# CntrlBoardV3B.net
KiCad netlist of a schematic drawn in EAGLE
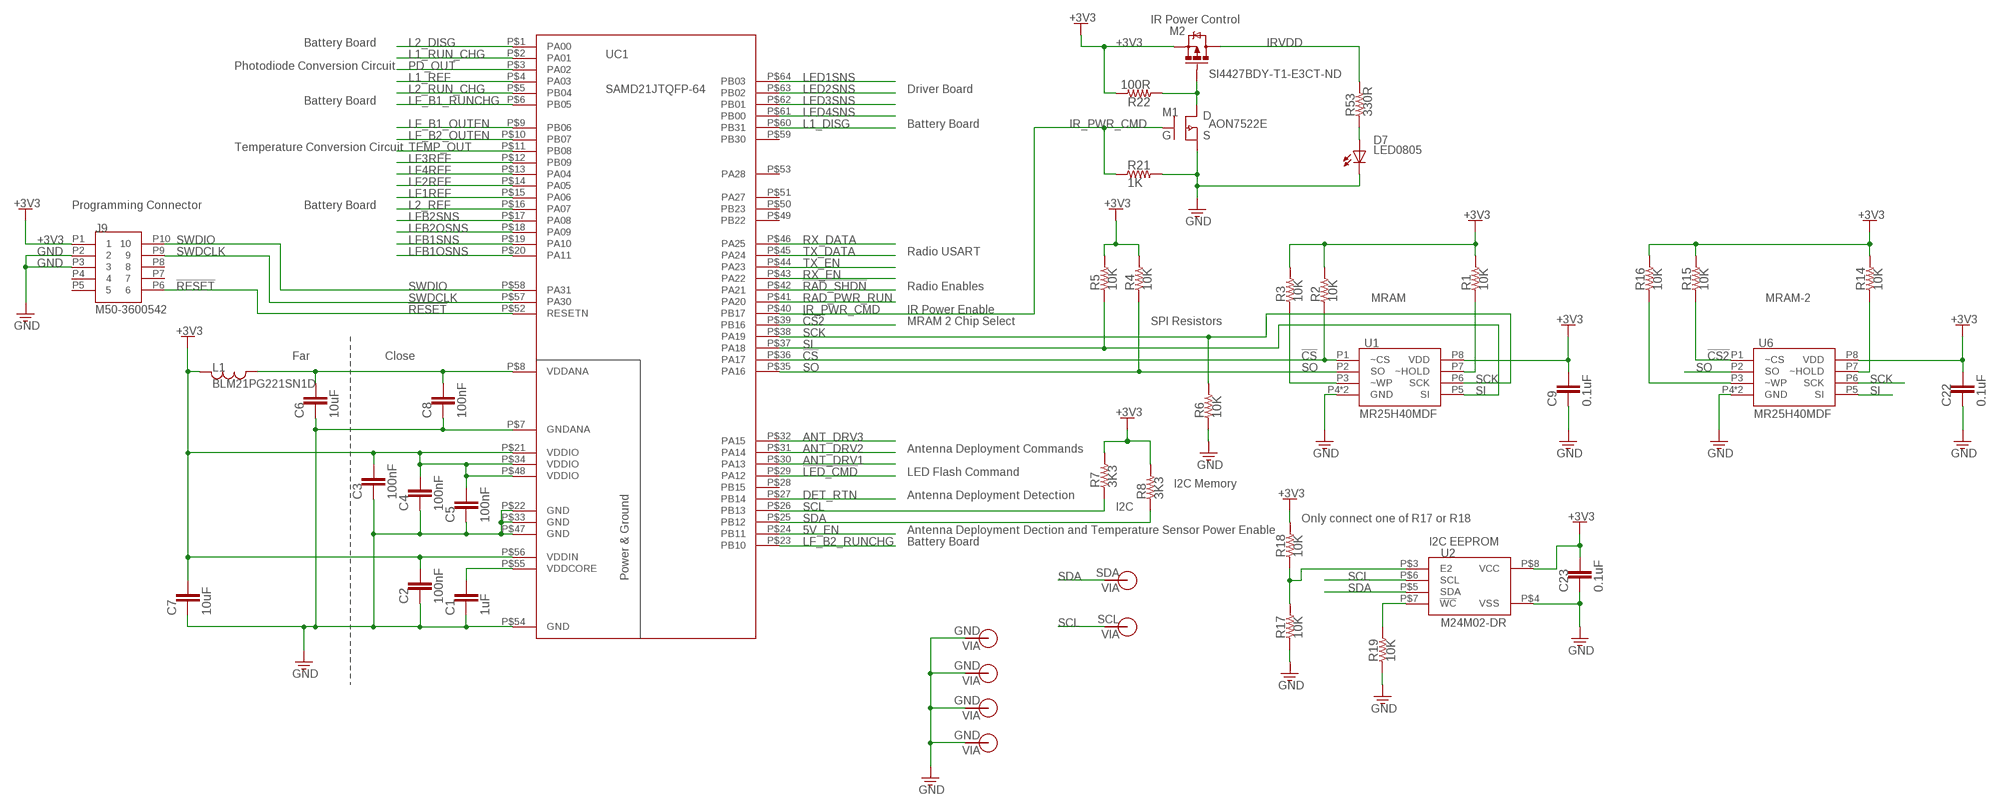
[diagram p0: schematic, sheet 1]
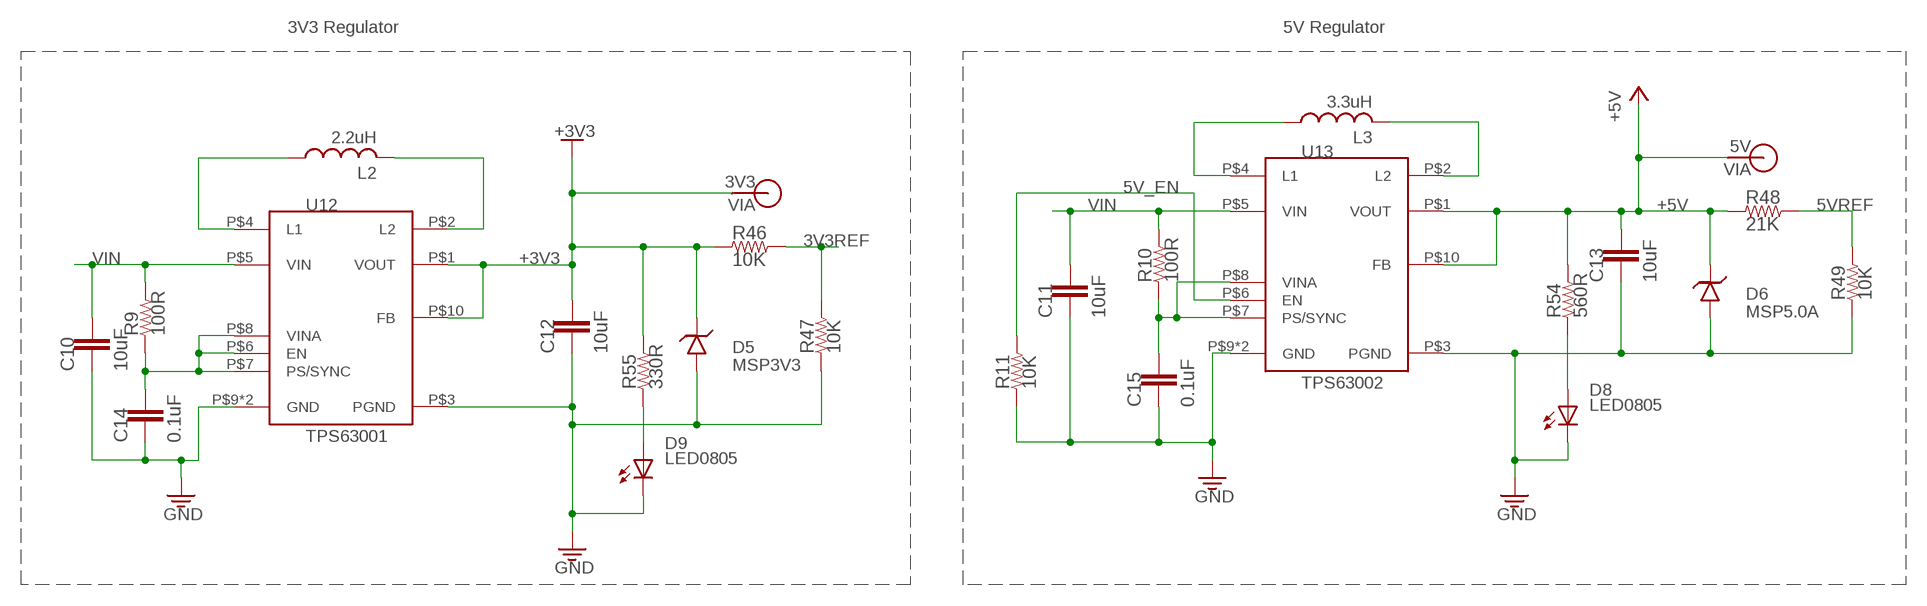
[diagram p1: schematic, sheet 2]
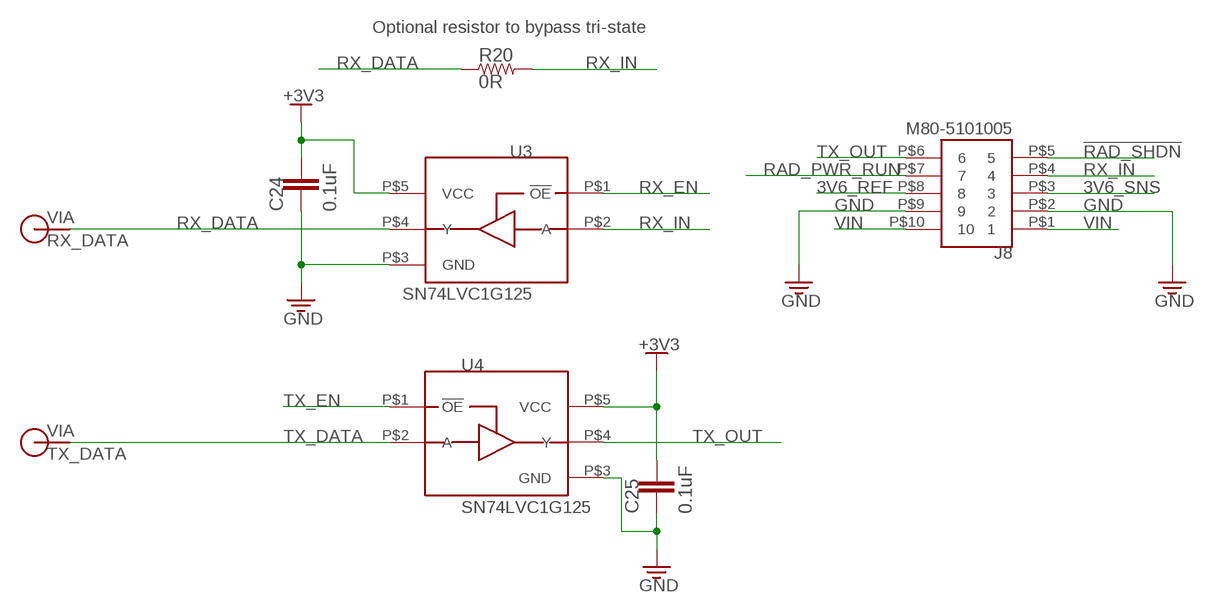
[diagram p2: schematic, sheet 3]
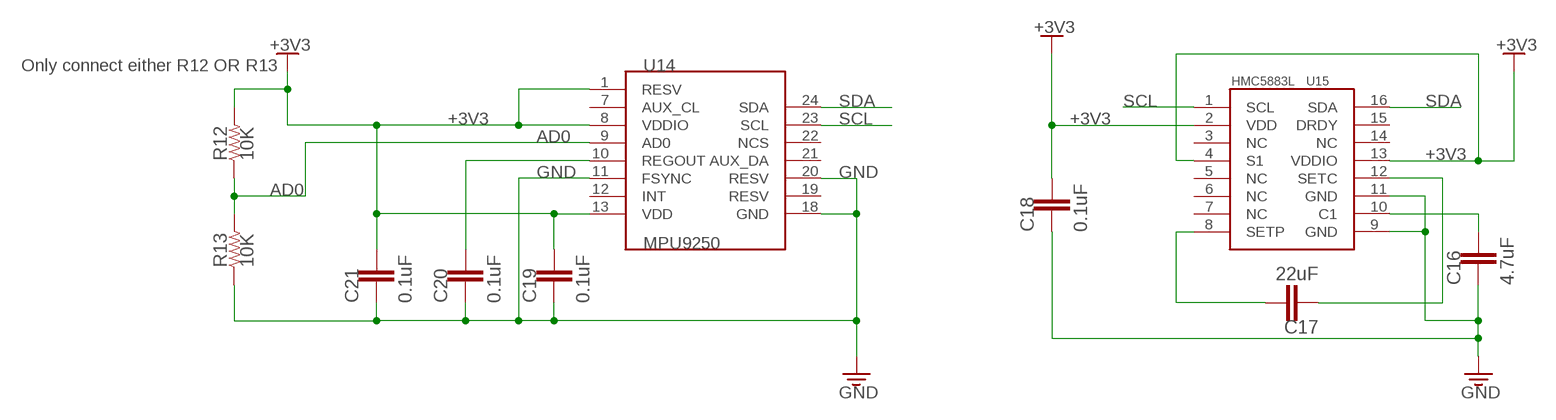
[diagram p3: schematic, sheet 4]
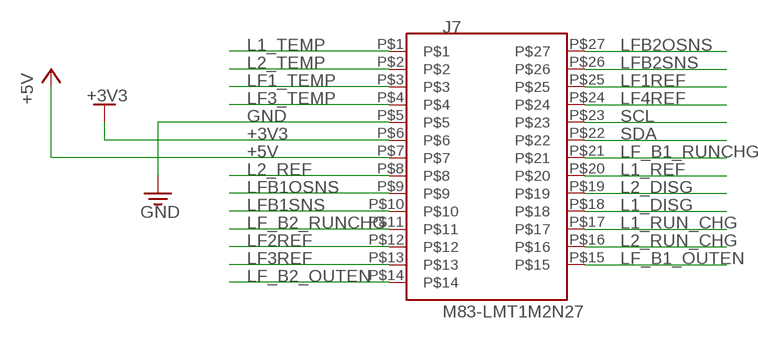
[diagram p4: schematic, sheet 5]
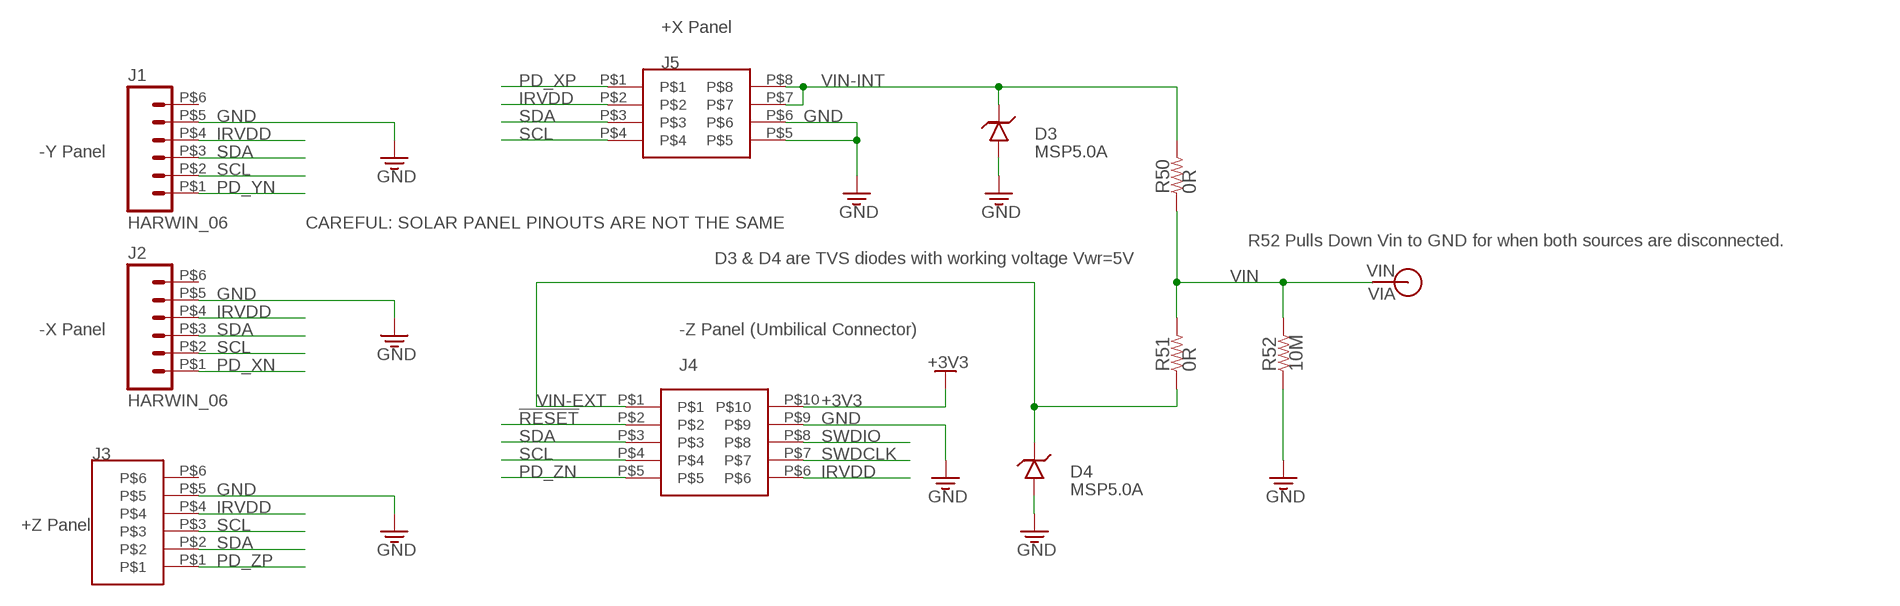
[diagram p5: schematic, sheet 6]
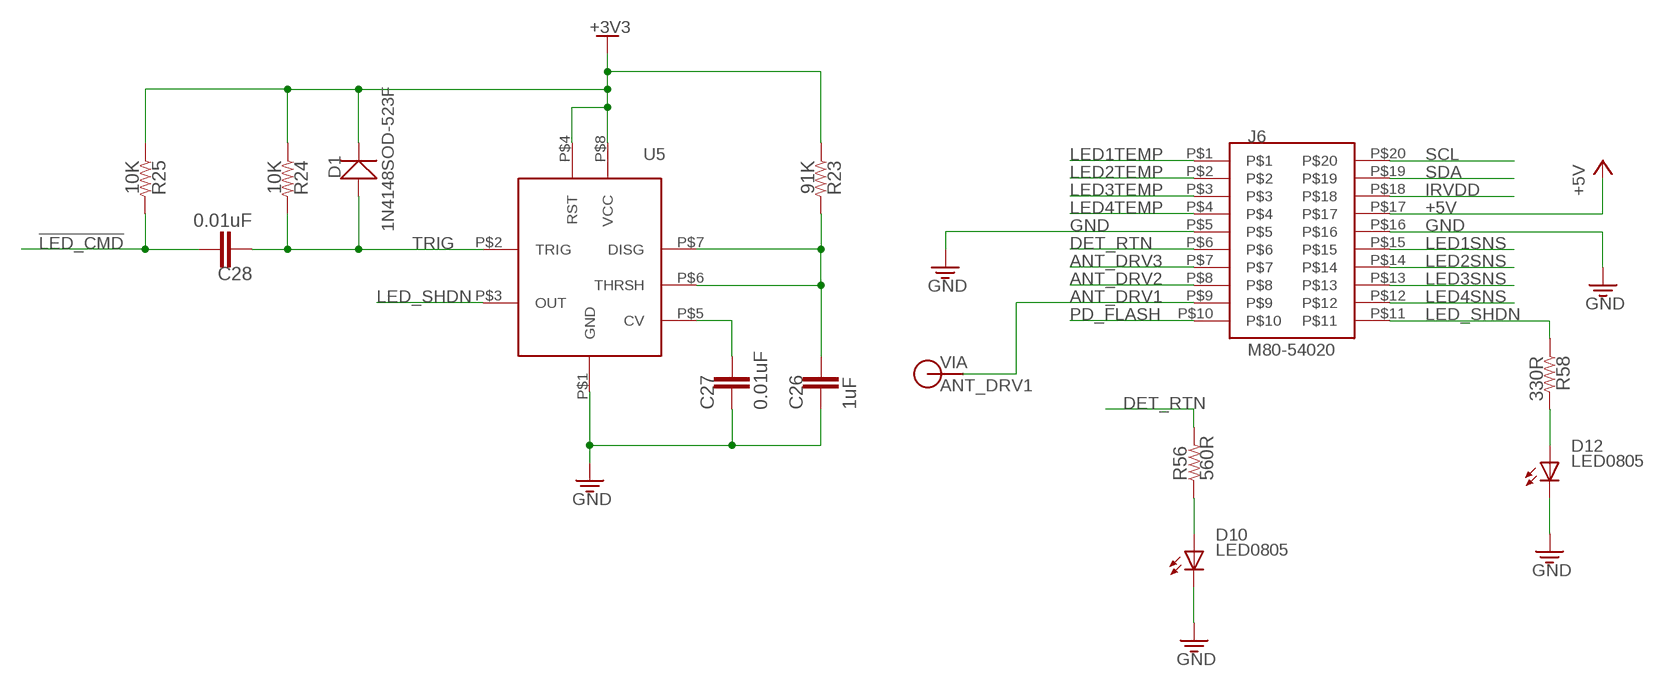
[diagram p6: schematic, sheet 7]
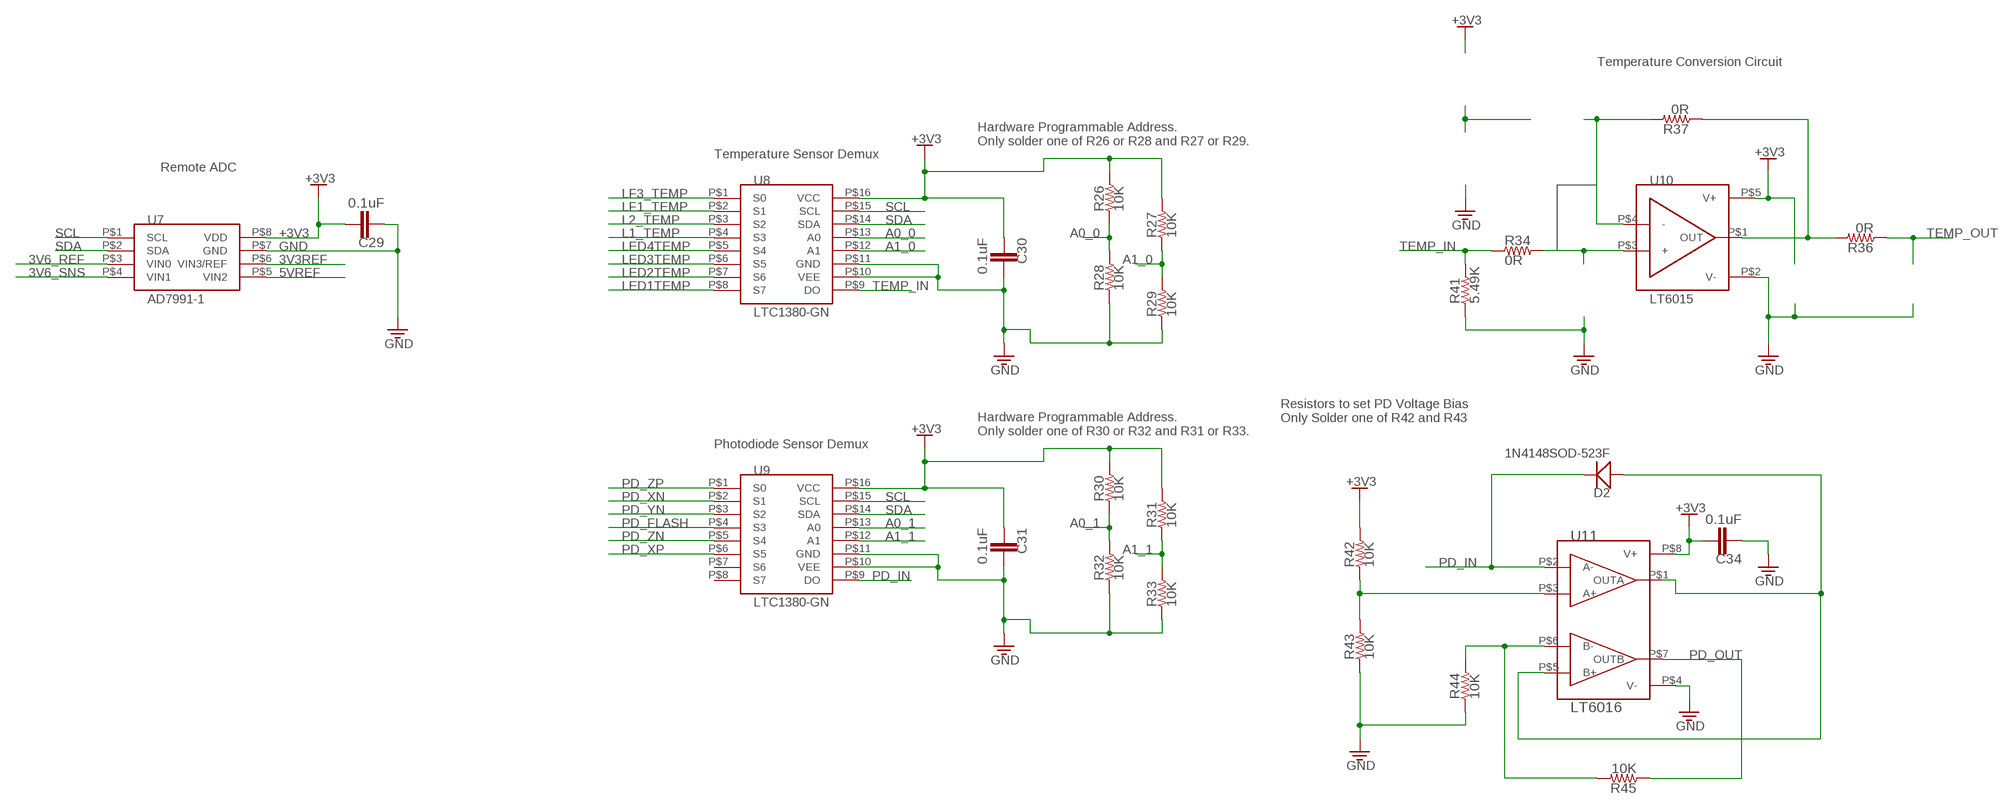
[diagram p7: schematic, sheet 8]

(export (version "E")
  (design (tool "Eeschema 10.0.6"))
  (components
    (comp (ref "C16")
      (value "4.7uF")
      (footprint "eagle-import:0805")
      (libsource (lib "eagle-import") (part "CAP0805"))
    )
    (comp (ref "C17")
      (value "22uF")
      (footprint "eagle-import:0805")
      (libsource (lib "eagle-import") (part "CAP0805"))
    )
    (comp (ref "C18")
      (value "0.1uF")
      (footprint "eagle-import:0805")
      (libsource (lib "eagle-import") (part "CAP0805"))
    )
    (comp (ref "C19")
      (value "0.1uF")
      (footprint "eagle-import:0805")
      (libsource (lib "eagle-import") (part "CAP0805"))
    )
    (comp (ref "C20")
      (value "0.1uF")
      (footprint "eagle-import:0805")
      (libsource (lib "eagle-import") (part "CAP0805"))
    )
    (comp (ref "C21")
      (value "0.1uF")
      (footprint "eagle-import:0805")
      (libsource (lib "eagle-import") (part "CAP0805"))
    )
    (comp (ref "R12")
      (value "10K")
      (footprint "eagle-import:0805")
      (libsource (lib "eagle-import") (part "RES0805"))
    )
    (comp (ref "R13")
      (value "10K")
      (footprint "eagle-import:0805")
      (libsource (lib "eagle-import") (part "RES0805"))
    )
    (comp (ref "U14")
      (value "MPU9250")
      (footprint "eagle-import:QFN-24-3X3")
      (libsource (lib "eagle-import") (part "MPU9250"))
    )
    (comp (ref "U15")
      (value "HMC5883L")
      (footprint "eagle-import:HMC5883L")
      (libsource (lib "eagle-import") (part "HMC5883L"))
    )
    (comp (ref "C26")
      (value "1uF")
      (footprint "eagle-import:0805")
      (libsource (lib "eagle-import") (part "CAP0805"))
    )
    (comp (ref "C27")
      (value "0.01uF")
      (footprint "eagle-import:0805")
      (libsource (lib "eagle-import") (part "CAP0805"))
    )
    (comp (ref "C28")
      (value "0.01uF")
      (footprint "eagle-import:0805")
      (libsource (lib "eagle-import") (part "CAP0805"))
    )
    (comp (ref "D1")
      (value "1N4148SOD-523F")
      (footprint "eagle-import:SOD-523F")
      (libsource (lib "eagle-import") (part "1N4148SMDSOD-523F"))
    )
    (comp (ref "D10")
      (value "LED0805")
      (footprint "eagle-import:0805-D")
      (libsource (lib "eagle-import") (part "LED0805"))
    )
    (comp (ref "D12")
      (value "LED0805")
      (footprint "eagle-import:0805-D")
      (libsource (lib "eagle-import") (part "LED0805"))
    )
    (comp (ref "J6")
      (value "M80-54020")
      (footprint "eagle-import:M80-54020")
      (libsource (lib "eagle-import") (part "M80-54020"))
    )
    (comp (ref "R23")
      (value "91K")
      (footprint "eagle-import:0805")
      (libsource (lib "eagle-import") (part "RES0805"))
    )
    (comp (ref "R24")
      (value "10K")
      (footprint "eagle-import:0805")
      (libsource (lib "eagle-import") (part "RES0805"))
    )
    (comp (ref "R25")
      (value "10K")
      (footprint "eagle-import:0805")
      (libsource (lib "eagle-import") (part "RES0805"))
    )
    (comp (ref "R56")
      (value "560R")
      (footprint "eagle-import:0805")
      (libsource (lib "eagle-import") (part "RES0805"))
    )
    (comp (ref "R58")
      (value "330R")
      (footprint "eagle-import:0805")
      (libsource (lib "eagle-import") (part "RES0805"))
    )
    (comp (ref "U5")
      (value "TLC555")
      (footprint "eagle-import:SO-8")
      (libsource (lib "eagle-import") (part "TLC555"))
    )
    (comp (ref "V6")
      (value "ANT_DRV1")
      (footprint "eagle-import:VIA-60MIL-SQ")
      (libsource (lib "eagle-import") (part "VIA60MIL-SQ"))
    )
    (comp (ref "D3")
      (value "MSP5.0A")
      (footprint "eagle-import:MICROSMP")
      (libsource (lib "eagle-import") (part "TVSMSP"))
    )
    (comp (ref "D4")
      (value "MSP5.0A")
      (footprint "eagle-import:MICROSMP")
      (libsource (lib "eagle-import") (part "TVSMSP"))
    )
    (comp (ref "J1")
      (value "HARWIN_06")
      (footprint "eagle-import:HARWIN_DATAMATE_6")
      (libsource (lib "eagle-import") (part "HARWIN_06"))
    )
    (comp (ref "J2")
      (value "HARWIN_06")
      (footprint "eagle-import:HARWIN_DATAMATE_6")
      (libsource (lib "eagle-import") (part "HARWIN_06"))
    )
    (comp (ref "J3")
      (value "M80-54006")
      (footprint "eagle-import:M80-54006")
      (libsource (lib "eagle-import") (part "M80-54006"))
    )
    (comp (ref "J4")
      (value "M80-54010")
      (footprint "eagle-import:M80-54010")
      (libsource (lib "eagle-import") (part "M80-54010"))
    )
    (comp (ref "J5")
      (value "M80-54008")
      (footprint "eagle-import:M80-54008")
      (libsource (lib "eagle-import") (part "M80-54008"))
    )
    (comp (ref "R50")
      (value "0R")
      (footprint "eagle-import:1210")
      (libsource (lib "eagle-import") (part "RES1210"))
    )
    (comp (ref "R51")
      (value "0R")
      (footprint "eagle-import:1210")
      (libsource (lib "eagle-import") (part "RES1210"))
    )
    (comp (ref "R52")
      (value "10M")
      (footprint "eagle-import:0805")
      (libsource (lib "eagle-import") (part "RES0805"))
    )
    (comp (ref "V3")
      (value "VIN")
      (footprint "eagle-import:VIA-60MIL-SQ")
      (libsource (lib "eagle-import") (part "VIA60MIL-SQ"))
    )
    (comp (ref "C10")
      (value "10uF")
      (footprint "eagle-import:0805")
      (libsource (lib "eagle-import") (part "CAP0805"))
    )
    (comp (ref "C11")
      (value "10uF")
      (footprint "eagle-import:0805")
      (libsource (lib "eagle-import") (part "CAP0805"))
    )
    (comp (ref "C12")
      (value "10uF")
      (footprint "eagle-import:0805")
      (libsource (lib "eagle-import") (part "CAP0805"))
    )
    (comp (ref "C13")
      (value "10uF")
      (footprint "eagle-import:0805")
      (libsource (lib "eagle-import") (part "CAP0805"))
    )
    (comp (ref "C14")
      (value "0.1uF")
      (footprint "eagle-import:0805")
      (libsource (lib "eagle-import") (part "CAP0805"))
    )
    (comp (ref "C15")
      (value "0.1uF")
      (footprint "eagle-import:0805")
      (libsource (lib "eagle-import") (part "CAP0805"))
    )
    (comp (ref "D5")
      (value "MSP3V3")
      (footprint "eagle-import:MICROSMP")
      (libsource (lib "eagle-import") (part "TVSMSP"))
    )
    (comp (ref "D6")
      (value "MSP5.0A")
      (footprint "eagle-import:MICROSMP")
      (libsource (lib "eagle-import") (part "TVSMSP"))
    )
    (comp (ref "D8")
      (value "LED0805")
      (footprint "eagle-import:0805-D")
      (libsource (lib "eagle-import") (part "LED0805"))
    )
    (comp (ref "D9")
      (value "LED0805")
      (footprint "eagle-import:0805-D")
      (libsource (lib "eagle-import") (part "LED0805"))
    )
    (comp (ref "L2")
      (value "2.2uH")
      (footprint "eagle-import:L3225M")
      (libsource (lib "eagle-import") (part "L-USL3225M"))
    )
    (comp (ref "L3")
      (value "3.3uH")
      (footprint "eagle-import:L3225M")
      (libsource (lib "eagle-import") (part "L-USL3225M"))
    )
    (comp (ref "R9")
      (value "100R")
      (footprint "eagle-import:0805")
      (libsource (lib "eagle-import") (part "RES0805"))
    )
    (comp (ref "R10")
      (value "100R")
      (footprint "eagle-import:0805")
      (libsource (lib "eagle-import") (part "RES0805"))
    )
    (comp (ref "R11")
      (value "10K")
      (footprint "eagle-import:0805")
      (libsource (lib "eagle-import") (part "RES0805"))
    )
    (comp (ref "R46")
      (value "10K")
      (footprint "eagle-import:0805")
      (libsource (lib "eagle-import") (part "RES0805"))
    )
    (comp (ref "R47")
      (value "10K")
      (footprint "eagle-import:0805")
      (libsource (lib "eagle-import") (part "RES0805"))
    )
    (comp (ref "R48")
      (value "21K")
      (footprint "eagle-import:0805")
      (libsource (lib "eagle-import") (part "RES0805"))
    )
    (comp (ref "R49")
      (value "10K")
      (footprint "eagle-import:0805")
      (libsource (lib "eagle-import") (part "RES0805"))
    )
    (comp (ref "R54")
      (value "560R")
      (footprint "eagle-import:0805")
      (libsource (lib "eagle-import") (part "RES0805"))
    )
    (comp (ref "R55")
      (value "330R")
      (footprint "eagle-import:0805")
      (libsource (lib "eagle-import") (part "RES0805"))
    )
    (comp (ref "U12")
      (value "TPS63001")
      (footprint "eagle-import:QFN10_POWERPAD")
      (libsource (lib "eagle-import") (part "TPS6300X"))
    )
    (comp (ref "U13")
      (value "TPS63002")
      (footprint "eagle-import:QFN10_POWERPAD")
      (libsource (lib "eagle-import") (part "TPS6300X"))
    )
    (comp (ref "V13")
      (value "3V3")
      (footprint "eagle-import:VIA-60MIL-SQ")
      (libsource (lib "eagle-import") (part "VIA60MIL-SQ"))
    )
    (comp (ref "V14")
      (value "5V")
      (footprint "eagle-import:VIA-60MIL-SQ")
      (libsource (lib "eagle-import") (part "VIA60MIL-SQ"))
    )
    (comp (ref "C1")
      (value "1uF")
      (footprint "eagle-import:0805")
      (libsource (lib "eagle-import") (part "CAP0805"))
    )
    (comp (ref "C2")
      (value "100nF")
      (footprint "eagle-import:0805")
      (libsource (lib "eagle-import") (part "CAP0805"))
    )
    (comp (ref "C3")
      (value "100nF")
      (footprint "eagle-import:0805")
      (libsource (lib "eagle-import") (part "CAP0805"))
    )
    (comp (ref "C4")
      (value "100nF")
      (footprint "eagle-import:0805")
      (libsource (lib "eagle-import") (part "CAP0805"))
    )
    (comp (ref "C5")
      (value "100nF")
      (footprint "eagle-import:0805")
      (libsource (lib "eagle-import") (part "CAP0805"))
    )
    (comp (ref "C6")
      (value "10uF")
      (footprint "eagle-import:0805")
      (libsource (lib "eagle-import") (part "CAP0805"))
    )
    (comp (ref "C7")
      (value "10uF")
      (footprint "eagle-import:0805")
      (libsource (lib "eagle-import") (part "CAP0805"))
    )
    (comp (ref "C8")
      (value "100nF")
      (footprint "eagle-import:0805")
      (libsource (lib "eagle-import") (part "CAP0805"))
    )
    (comp (ref "C9")
      (value "0.1uF")
      (footprint "eagle-import:0805")
      (libsource (lib "eagle-import") (part "CAP0805"))
    )
    (comp (ref "C22")
      (value "0.1uF")
      (footprint "eagle-import:0805")
      (libsource (lib "eagle-import") (part "CAP0805"))
    )
    (comp (ref "C23")
      (value "0.1uF")
      (footprint "eagle-import:0805")
      (libsource (lib "eagle-import") (part "CAP0805"))
    )
    (comp (ref "D7")
      (value "LED0805")
      (footprint "eagle-import:0805-D")
      (libsource (lib "eagle-import") (part "LED0805"))
    )
    (comp (ref "J9")
      (value "M50-3600542")
      (footprint "eagle-import:10PINMALE")
      (libsource (lib "eagle-import") (part "10PINMALE"))
    )
    (comp (ref "L1")
      (value "BLM21PG221SN1D")
      (footprint "eagle-import:0805")
      (libsource (lib "eagle-import") (part "FERRITE"))
    )
    (comp (ref "M1")
      (value "AON7522E")
      (footprint "eagle-import:DFN-3X3-8")
      (libsource (lib "eagle-import") (part "AON7522E"))
    )
    (comp (ref "M2")
      (value "SI4427BDY-T1-E3CT-ND")
      (footprint "eagle-import:SO08")
      (libsource (lib "eagle-import") (part "POWERPMOS"))
    )
    (comp (ref "R1")
      (value "10K")
      (footprint "eagle-import:0805")
      (libsource (lib "eagle-import") (part "RES0805"))
    )
    (comp (ref "R2")
      (value "10K")
      (footprint "eagle-import:0805")
      (libsource (lib "eagle-import") (part "RES0805"))
    )
    (comp (ref "R3")
      (value "10K")
      (footprint "eagle-import:0805")
      (libsource (lib "eagle-import") (part "RES0805"))
    )
    (comp (ref "R4")
      (value "10K")
      (footprint "eagle-import:0805")
      (libsource (lib "eagle-import") (part "RES0805"))
    )
    (comp (ref "R5")
      (value "10K")
      (footprint "eagle-import:0805")
      (libsource (lib "eagle-import") (part "RES0805"))
    )
    (comp (ref "R6")
      (value "10K")
      (footprint "eagle-import:0805")
      (libsource (lib "eagle-import") (part "RES0805"))
    )
    (comp (ref "R7")
      (value "3K3")
      (footprint "eagle-import:0805")
      (libsource (lib "eagle-import") (part "RES0805"))
    )
    (comp (ref "R8")
      (value "3K3")
      (footprint "eagle-import:0805")
      (libsource (lib "eagle-import") (part "RES0805"))
    )
    (comp (ref "R14")
      (value "10K")
      (footprint "eagle-import:0805")
      (libsource (lib "eagle-import") (part "RES0805"))
    )
    (comp (ref "R15")
      (value "10K")
      (footprint "eagle-import:0805")
      (libsource (lib "eagle-import") (part "RES0805"))
    )
    (comp (ref "R16")
      (value "10K")
      (footprint "eagle-import:0805")
      (libsource (lib "eagle-import") (part "RES0805"))
    )
    (comp (ref "R17")
      (value "10K")
      (footprint "eagle-import:0805")
      (libsource (lib "eagle-import") (part "RES0805"))
    )
    (comp (ref "R18")
      (value "10K")
      (footprint "eagle-import:0805")
      (libsource (lib "eagle-import") (part "RES0805"))
    )
    (comp (ref "R19")
      (value "10K")
      (footprint "eagle-import:0805")
      (libsource (lib "eagle-import") (part "RES0805"))
    )
    (comp (ref "R21")
      (value "1K")
      (footprint "eagle-import:0805")
      (libsource (lib "eagle-import") (part "RES0805"))
    )
    (comp (ref "R22")
      (value "100R")
      (footprint "eagle-import:0805")
      (libsource (lib "eagle-import") (part "RES0805"))
    )
    (comp (ref "R53")
      (value "330R")
      (footprint "eagle-import:0805")
      (libsource (lib "eagle-import") (part "RES0805"))
    )
    (comp (ref "U1")
      (value "MR25H40MDF")
      (footprint "eagle-import:8PXMO-229")
      (libsource (lib "eagle-import") (part "MR2XHXX"))
    )
    (comp (ref "U2")
      (value "M24M02-DR")
      (footprint "eagle-import:SO-8")
      (libsource (lib "eagle-import") (part "M24M02-DR"))
    )
    (comp (ref "U6")
      (value "MR25H40MDF")
      (footprint "eagle-import:8PXMO-229")
      (libsource (lib "eagle-import") (part "MR2XHXX"))
    )
    (comp (ref "UC1")
      (value "SAMD21JTQFP-64")
      (footprint "eagle-import:TQFP-64")
      (libsource (lib "eagle-import") (part "SAMD21JTQFP-64"))
    )
    (comp (ref "V4")
      (value "SDA")
      (footprint "eagle-import:VIA-60MIL-SQ")
      (libsource (lib "eagle-import") (part "VIA60MIL-SQ"))
    )
    (comp (ref "V5")
      (value "SCL")
      (footprint "eagle-import:VIA-60MIL-SQ")
      (libsource (lib "eagle-import") (part "VIA60MIL-SQ"))
    )
    (comp (ref "V9")
      (value "GND")
      (footprint "eagle-import:VIA-60MIL-SQ")
      (libsource (lib "eagle-import") (part "VIA60MIL-SQ"))
    )
    (comp (ref "V10")
      (value "GND")
      (footprint "eagle-import:VIA-60MIL-SQ")
      (libsource (lib "eagle-import") (part "VIA60MIL-SQ"))
    )
    (comp (ref "V11")
      (value "GND")
      (footprint "eagle-import:VIA-60MIL-SQ")
      (libsource (lib "eagle-import") (part "VIA60MIL-SQ"))
    )
    (comp (ref "V12")
      (value "GND")
      (footprint "eagle-import:VIA-60MIL-SQ")
      (libsource (lib "eagle-import") (part "VIA60MIL-SQ"))
    )
    (comp (ref "C24")
      (value "0.1uF")
      (footprint "eagle-import:0805")
      (libsource (lib "eagle-import") (part "CAP0805"))
    )
    (comp (ref "C25")
      (value "0.1uF")
      (footprint "eagle-import:0805")
      (libsource (lib "eagle-import") (part "CAP0805"))
    )
    (comp (ref "J8")
      (value "M80-5101005")
      (footprint "eagle-import:M80-510")
      (libsource (lib "eagle-import") (part "M80-5101005"))
    )
    (comp (ref "R20")
      (value "0R")
      (footprint "eagle-import:0805")
      (libsource (lib "eagle-import") (part "RES0805"))
    )
    (comp (ref "U3")
      (value "SN74LVC1G125")
      (footprint "eagle-import:TSOT23-5")
      (libsource (lib "eagle-import") (part "SN74LVC1G125"))
    )
    (comp (ref "U4")
      (value "SN74LVC1G125")
      (footprint "eagle-import:TSOT23-5")
      (libsource (lib "eagle-import") (part "SN74LVC1G125"))
    )
    (comp (ref "V1")
      (value "RX_DATA")
      (footprint "eagle-import:VIA-60MIL-SQ")
      (libsource (lib "eagle-import") (part "VIA60MIL-SQ"))
    )
    (comp (ref "V2")
      (value "TX_DATA")
      (footprint "eagle-import:VIA-60MIL-SQ")
      (libsource (lib "eagle-import") (part "VIA60MIL-SQ"))
    )
    (comp (ref "C29")
      (value "0.1uF")
      (footprint "eagle-import:0805")
      (libsource (lib "eagle-import") (part "CAP0805"))
    )
    (comp (ref "C30")
      (value "0.1uF")
      (footprint "eagle-import:0805")
      (libsource (lib "eagle-import") (part "CAP0805"))
    )
    (comp (ref "C31")
      (value "0.1uF")
      (footprint "eagle-import:0805")
      (libsource (lib "eagle-import") (part "CAP0805"))
    )
    (comp (ref "C34")
      (value "0.1uF")
      (footprint "eagle-import:0805")
      (libsource (lib "eagle-import") (part "CAP0805"))
    )
    (comp (ref "D2")
      (value "1N4148SOD-523F")
      (footprint "eagle-import:SOD-523F")
      (libsource (lib "eagle-import") (part "1N4148SMDSOD-523F"))
    )
    (comp (ref "R26")
      (value "10K")
      (footprint "eagle-import:0805")
      (libsource (lib "eagle-import") (part "RES0805"))
    )
    (comp (ref "R27")
      (value "10K")
      (footprint "eagle-import:0805")
      (libsource (lib "eagle-import") (part "RES0805"))
    )
    (comp (ref "R28")
      (value "10K")
      (footprint "eagle-import:0805")
      (libsource (lib "eagle-import") (part "RES0805"))
    )
    (comp (ref "R29")
      (value "10K")
      (footprint "eagle-import:0805")
      (libsource (lib "eagle-import") (part "RES0805"))
    )
    (comp (ref "R30")
      (value "10K")
      (footprint "eagle-import:0805")
      (libsource (lib "eagle-import") (part "RES0805"))
    )
    (comp (ref "R31")
      (value "10K")
      (footprint "eagle-import:0805")
      (libsource (lib "eagle-import") (part "RES0805"))
    )
    (comp (ref "R32")
      (value "10K")
      (footprint "eagle-import:0805")
      (libsource (lib "eagle-import") (part "RES0805"))
    )
    (comp (ref "R33")
      (value "10K")
      (footprint "eagle-import:0805")
      (libsource (lib "eagle-import") (part "RES0805"))
    )
    (comp (ref "R34")
      (value "0R")
      (footprint "eagle-import:0805")
      (libsource (lib "eagle-import") (part "RES0805"))
    )
    (comp (ref "R36")
      (value "0R")
      (footprint "eagle-import:0805")
      (libsource (lib "eagle-import") (part "RES0805"))
    )
    (comp (ref "R37")
      (value "0R")
      (footprint "eagle-import:0805")
      (libsource (lib "eagle-import") (part "RES0805"))
    )
    (comp (ref "R41")
      (value "5.49K")
      (footprint "eagle-import:0805")
      (libsource (lib "eagle-import") (part "RES0805"))
    )
    (comp (ref "R42")
      (value "10K")
      (footprint "eagle-import:0805")
      (libsource (lib "eagle-import") (part "RES0805"))
    )
    (comp (ref "R43")
      (value "10K")
      (footprint "eagle-import:0805")
      (libsource (lib "eagle-import") (part "RES0805"))
    )
    (comp (ref "R44")
      (value "10K")
      (footprint "eagle-import:0805")
      (libsource (lib "eagle-import") (part "RES0805"))
    )
    (comp (ref "R45")
      (value "10K")
      (footprint "eagle-import:0805")
      (libsource (lib "eagle-import") (part "RES0805"))
    )
    (comp (ref "U7")
      (value "AD7991-1")
      (footprint "eagle-import:SOT-23-8")
      (libsource (lib "eagle-import") (part "AD7991-1"))
    )
    (comp (ref "U8")
      (value "LTC1380-GN")
      (footprint "eagle-import:SSOP-16-NARROW")
      (libsource (lib "eagle-import") (part "LTC1380-GN"))
    )
    (comp (ref "U9")
      (value "LTC1380-GN")
      (footprint "eagle-import:SSOP-16-NARROW")
      (libsource (lib "eagle-import") (part "LTC1380-GN"))
    )
    (comp (ref "U10")
      (value "LT6015")
      (footprint "eagle-import:TSOT23-5")
      (libsource (lib "eagle-import") (part "LT6015"))
    )
    (comp (ref "U11")
      (value "LT6016")
      (footprint "eagle-import:MSOP-8")
      (libsource (lib "eagle-import") (part "LT6016"))
    )
    (comp (ref "J7")
      (value "M83-LMT1M2N27")
      (footprint "eagle-import:M83-LMT1M2N27")
      (libsource (lib "eagle-import") (part "M83-LMT1M2N27"))
    )
  )
  (nets
    (net (code "1") (name "+3V3") (class "Default")
      (node (ref "C12") (pin "1") (pinfunction "P$1_1") (pintype "passive"))
      (node (ref "C18") (pin "1") (pinfunction "P$1_1") (pintype "passive"))
      (node (ref "C19") (pin "1") (pinfunction "P$1_1") (pintype "passive"))
      (node (ref "C2") (pin "1") (pinfunction "P$1_1") (pintype "passive"))
      (node (ref "C21") (pin "1") (pinfunction "P$1_1") (pintype "passive"))
      (node (ref "C22") (pin "1") (pinfunction "P$1_1") (pintype "passive"))
      (node (ref "C23") (pin "1") (pinfunction "P$1_1") (pintype "passive"))
      (node (ref "C24") (pin "1") (pinfunction "P$1_1") (pintype "passive"))
      (node (ref "C25") (pin "1") (pinfunction "P$1_1") (pintype "passive"))
      (node (ref "C29") (pin "1") (pinfunction "P$1_1") (pintype "passive"))
      (node (ref "C3") (pin "1") (pinfunction "P$1_1") (pintype "passive"))
      (node (ref "C30") (pin "2") (pinfunction "P$2_2") (pintype "passive"))
      (node (ref "C31") (pin "2") (pinfunction "P$2_2") (pintype "passive"))
      (node (ref "C34") (pin "1") (pinfunction "P$1_1") (pintype "passive"))
      (node (ref "C4") (pin "1") (pinfunction "P$1_1") (pintype "passive"))
      (node (ref "C5") (pin "1") (pinfunction "P$1_1") (pintype "passive"))
      (node (ref "C7") (pin "1") (pinfunction "P$1_1") (pintype "passive"))
      (node (ref "C9") (pin "1") (pinfunction "P$1_1") (pintype "passive"))
      (node (ref "D1") (pin "C") (pinfunction "C_C") (pintype "bidirectional"))
      (node (ref "D5") (pin "C") (pinfunction "C_C") (pintype "bidirectional"))
      (node (ref "J4") (pin "P$10") (pinfunction "P$10_P$10") (pintype "bidirectional"))
      (node (ref "J7") (pin "P$6") (pinfunction "P$6_P$6") (pintype "bidirectional"))
      (node (ref "J9") (pin "P1") (pinfunction "1_P1") (pintype "bidirectional"))
      (node (ref "L1") (pin "1") (pinfunction "P$1_1") (pintype "passive"))
      (node (ref "M2") (pin "1") (pinfunction "S_1") (pintype "passive"))
      (node (ref "M2") (pin "2") (pinfunction "S_2") (pintype "passive"))
      (node (ref "M2") (pin "3") (pinfunction "S_3") (pintype "passive"))
      (node (ref "R1") (pin "2") (pinfunction "2_2") (pintype "passive"))
      (node (ref "R12") (pin "2") (pinfunction "2_2") (pintype "passive"))
      (node (ref "R14") (pin "2") (pinfunction "2_2") (pintype "passive"))
      (node (ref "R15") (pin "2") (pinfunction "2_2") (pintype "passive"))
      (node (ref "R16") (pin "2") (pinfunction "2_2") (pintype "passive"))
      (node (ref "R18") (pin "2") (pinfunction "2_2") (pintype "passive"))
      (node (ref "R2") (pin "2") (pinfunction "2_2") (pintype "passive"))
      (node (ref "R22") (pin "2") (pinfunction "2_2") (pintype "passive"))
      (node (ref "R23") (pin "1") (pinfunction "1_1") (pintype "passive"))
      (node (ref "R24") (pin "1") (pinfunction "1_1") (pintype "passive"))
      (node (ref "R25") (pin "1") (pinfunction "1_1") (pintype "passive"))
      (node (ref "R26") (pin "2") (pinfunction "2_2") (pintype "passive"))
      (node (ref "R27") (pin "2") (pinfunction "2_2") (pintype "passive"))
      (node (ref "R3") (pin "2") (pinfunction "2_2") (pintype "passive"))
      (node (ref "R30") (pin "2") (pinfunction "2_2") (pintype "passive"))
      (node (ref "R31") (pin "2") (pinfunction "2_2") (pintype "passive"))
      (node (ref "R4") (pin "2") (pinfunction "2_2") (pintype "passive"))
      (node (ref "R42") (pin "2") (pinfunction "2_2") (pintype "passive"))
      (node (ref "R46") (pin "1") (pinfunction "1_1") (pintype "passive"))
      (node (ref "R5") (pin "2") (pinfunction "2_2") (pintype "passive"))
      (node (ref "R55") (pin "2") (pinfunction "2_2") (pintype "passive"))
      (node (ref "R7") (pin "2") (pinfunction "2_2") (pintype "passive"))
      (node (ref "R8") (pin "2") (pinfunction "2_2") (pintype "passive"))
      (node (ref "U1") (pin "P8") (pinfunction "VDD_P8") (pintype "bidirectional"))
      (node (ref "U10") (pin "P$5") (pinfunction "V+_P$5") (pintype "bidirectional"))
      (node (ref "U11") (pin "P$8") (pinfunction "V+_P$8") (pintype "bidirectional"))
      (node (ref "U12") (pin "P$1") (pinfunction "VOUT_P$1") (pintype "output"))
      (node (ref "U12") (pin "P$10") (pinfunction "FB_P$10") (pintype "input"))
      (node (ref "U14") (pin "1") (pinfunction "RESV_1") (pintype "bidirectional"))
      (node (ref "U14") (pin "13") (pinfunction "VDD_13") (pintype "bidirectional"))
      (node (ref "U14") (pin "8") (pinfunction "VDDIO_8") (pintype "bidirectional"))
      (node (ref "U15") (pin "13") (pinfunction "VDDIO_13") (pintype "bidirectional"))
      (node (ref "U15") (pin "2") (pinfunction "VDD_2") (pintype "bidirectional"))
      (node (ref "U15") (pin "4") (pinfunction "S1_4") (pintype "bidirectional"))
      (node (ref "U2") (pin "P$8") (pinfunction "VCC_P$8") (pintype "bidirectional"))
      (node (ref "U3") (pin "P$5") (pinfunction "VCC_P$5") (pintype "bidirectional"))
      (node (ref "U4") (pin "P$5") (pinfunction "VCC_P$5") (pintype "bidirectional"))
      (node (ref "U5") (pin "P$4") (pinfunction "RST_P$4") (pintype "bidirectional"))
      (node (ref "U5") (pin "P$8") (pinfunction "VCC_P$8") (pintype "bidirectional"))
      (node (ref "U6") (pin "P8") (pinfunction "VDD_P8") (pintype "bidirectional"))
      (node (ref "U7") (pin "P$8") (pinfunction "VDD_P$8") (pintype "bidirectional"))
      (node (ref "U8") (pin "P$16") (pinfunction "VCC_P$16") (pintype "bidirectional"))
      (node (ref "U9") (pin "P$16") (pinfunction "VCC_P$16") (pintype "bidirectional"))
      (node (ref "UC1") (pin "P$21") (pinfunction "VDDIO_P$21") (pintype "power_in"))
      (node (ref "UC1") (pin "P$34") (pinfunction "VDDIO_P$34") (pintype "power_in"))
      (node (ref "UC1") (pin "P$48") (pinfunction "VDDIO_P$48") (pintype "power_in"))
      (node (ref "UC1") (pin "P$56") (pinfunction "VDDIN_P$56") (pintype "power_in"))
      (node (ref "V13") (pin "P$1") (pinfunction "P$1_P$1") (pintype "bidirectional"))
    )
    (net (code "2") (name "+5V") (class "Default")
      (node (ref "C13") (pin "1") (pinfunction "P$1_1") (pintype "passive"))
      (node (ref "D6") (pin "C") (pinfunction "C_C") (pintype "bidirectional"))
      (node (ref "J6") (pin "P$17") (pinfunction "P$17_P$17") (pintype "bidirectional"))
      (node (ref "J7") (pin "P$7") (pinfunction "P$7_P$7") (pintype "bidirectional"))
      (node (ref "R48") (pin "1") (pinfunction "1_1") (pintype "passive"))
      (node (ref "R54") (pin "2") (pinfunction "2_2") (pintype "passive"))
      (node (ref "U13") (pin "P$1") (pinfunction "VOUT_P$1") (pintype "output"))
      (node (ref "U13") (pin "P$10") (pinfunction "FB_P$10") (pintype "input"))
      (node (ref "V14") (pin "P$1") (pinfunction "P$1_P$1") (pintype "bidirectional"))
    )
    (net (code "3") (name "3V3REF") (class "Default")
      (node (ref "R46") (pin "2") (pinfunction "2_2") (pintype "passive"))
      (node (ref "R47") (pin "2") (pinfunction "2_2") (pintype "passive"))
      (node (ref "U7") (pin "P$6") (pinfunction "VIN3/REF_P$6") (pintype "bidirectional"))
    )
    (net (code "4") (name "3V6_REF") (class "Default")
      (node (ref "J8") (pin "P$8") (pinfunction "8_P$8") (pintype "bidirectional"))
      (node (ref "U7") (pin "P$3") (pinfunction "VIN0_P$3") (pintype "bidirectional"))
    )
    (net (code "5") (name "3V6_SNS") (class "Default")
      (node (ref "J8") (pin "P$3") (pinfunction "3_P$3") (pintype "bidirectional"))
      (node (ref "U7") (pin "P$4") (pinfunction "VIN1_P$4") (pintype "bidirectional"))
    )
    (net (code "6") (name "5VREF") (class "Default")
      (node (ref "R48") (pin "2") (pinfunction "2_2") (pintype "passive"))
      (node (ref "R49") (pin "2") (pinfunction "2_2") (pintype "passive"))
      (node (ref "U7") (pin "P$5") (pinfunction "VIN2_P$5") (pintype "bidirectional"))
    )
    (net (code "7") (name "5V_EN") (class "Default")
      (node (ref "R11") (pin "2") (pinfunction "2_2") (pintype "passive"))
      (node (ref "U13") (pin "P$6") (pinfunction "EN_P$6") (pintype "input"))
      (node (ref "UC1") (pin "P$24") (pinfunction "PB11_P$24") (pintype "bidirectional"))
    )
    (net (code "8") (name "A0_0") (class "Default")
      (node (ref "R26") (pin "1") (pinfunction "1_1") (pintype "passive"))
      (node (ref "R28") (pin "2") (pinfunction "2_2") (pintype "passive"))
      (node (ref "U8") (pin "P$13") (pinfunction "A0_P$13") (pintype "bidirectional"))
    )
    (net (code "9") (name "A0_1") (class "Default")
      (node (ref "R30") (pin "1") (pinfunction "1_1") (pintype "passive"))
      (node (ref "R32") (pin "2") (pinfunction "2_2") (pintype "passive"))
      (node (ref "U9") (pin "P$13") (pinfunction "A0_P$13") (pintype "bidirectional"))
    )
    (net (code "10") (name "A1_0") (class "Default")
      (node (ref "R27") (pin "1") (pinfunction "1_1") (pintype "passive"))
      (node (ref "R29") (pin "2") (pinfunction "2_2") (pintype "passive"))
      (node (ref "U8") (pin "P$12") (pinfunction "A1_P$12") (pintype "bidirectional"))
    )
    (net (code "11") (name "A1_1") (class "Default")
      (node (ref "R31") (pin "1") (pinfunction "1_1") (pintype "passive"))
      (node (ref "R33") (pin "2") (pinfunction "2_2") (pintype "passive"))
      (node (ref "U9") (pin "P$12") (pinfunction "A1_P$12") (pintype "bidirectional"))
    )
    (net (code "12") (name "AD0") (class "Default")
      (node (ref "R12") (pin "1") (pinfunction "1_1") (pintype "passive"))
      (node (ref "R13") (pin "2") (pinfunction "2_2") (pintype "passive"))
      (node (ref "U14") (pin "9") (pinfunction "AD0_9") (pintype "bidirectional"))
    )
    (net (code "13") (name "ANT_DRV1") (class "Default")
      (node (ref "J6") (pin "P$9") (pinfunction "P$9_P$9") (pintype "bidirectional"))
      (node (ref "UC1") (pin "P$30") (pinfunction "PA13_P$30") (pintype "bidirectional"))
      (node (ref "V6") (pin "P$1") (pinfunction "P$1_P$1") (pintype "bidirectional"))
    )
    (net (code "14") (name "ANT_DRV2") (class "Default")
      (node (ref "J6") (pin "P$8") (pinfunction "P$8_P$8") (pintype "bidirectional"))
      (node (ref "UC1") (pin "P$31") (pinfunction "PA14_P$31") (pintype "bidirectional"))
    )
    (net (code "15") (name "ANT_DRV3") (class "Default")
      (node (ref "J6") (pin "P$7") (pinfunction "P$7_P$7") (pintype "bidirectional"))
      (node (ref "UC1") (pin "P$32") (pinfunction "PA15_P$32") (pintype "bidirectional"))
    )
    (net (code "16") (name "DET_RTN") (class "Default")
      (node (ref "J6") (pin "P$6") (pinfunction "P$6_P$6") (pintype "bidirectional"))
      (node (ref "R56") (pin "2") (pinfunction "2_2") (pintype "passive"))
      (node (ref "UC1") (pin "P$27") (pinfunction "PB14_P$27") (pintype "bidirectional"))
    )
    (net (code "17") (name "GND") (class "Default")
      (node (ref "C1") (pin "2") (pinfunction "P$2_2") (pintype "passive"))
      (node (ref "C10") (pin "2") (pinfunction "P$2_2") (pintype "passive"))
      (node (ref "C11") (pin "2") (pinfunction "P$2_2") (pintype "passive"))
      (node (ref "C12") (pin "2") (pinfunction "P$2_2") (pintype "passive"))
      (node (ref "C13") (pin "2") (pinfunction "P$2_2") (pintype "passive"))
      (node (ref "C14") (pin "2") (pinfunction "P$2_2") (pintype "passive"))
      (node (ref "C15") (pin "2") (pinfunction "P$2_2") (pintype "passive"))
      (node (ref "C16") (pin "2") (pinfunction "P$2_2") (pintype "passive"))
      (node (ref "C18") (pin "2") (pinfunction "P$2_2") (pintype "passive"))
      (node (ref "C19") (pin "2") (pinfunction "P$2_2") (pintype "passive"))
      (node (ref "C2") (pin "2") (pinfunction "P$2_2") (pintype "passive"))
      (node (ref "C20") (pin "2") (pinfunction "P$2_2") (pintype "passive"))
      (node (ref "C21") (pin "2") (pinfunction "P$2_2") (pintype "passive"))
      (node (ref "C22") (pin "2") (pinfunction "P$2_2") (pintype "passive"))
      (node (ref "C23") (pin "2") (pinfunction "P$2_2") (pintype "passive"))
      (node (ref "C24") (pin "2") (pinfunction "P$2_2") (pintype "passive"))
      (node (ref "C25") (pin "2") (pinfunction "P$2_2") (pintype "passive"))
      (node (ref "C26") (pin "2") (pinfunction "P$2_2") (pintype "passive"))
      (node (ref "C27") (pin "2") (pinfunction "P$2_2") (pintype "passive"))
      (node (ref "C29") (pin "2") (pinfunction "P$2_2") (pintype "passive"))
      (node (ref "C3") (pin "2") (pinfunction "P$2_2") (pintype "passive"))
      (node (ref "C30") (pin "1") (pinfunction "P$1_1") (pintype "passive"))
      (node (ref "C31") (pin "1") (pinfunction "P$1_1") (pintype "passive"))
      (node (ref "C34") (pin "2") (pinfunction "P$2_2") (pintype "passive"))
      (node (ref "C4") (pin "2") (pinfunction "P$2_2") (pintype "passive"))
      (node (ref "C5") (pin "2") (pinfunction "P$2_2") (pintype "passive"))
      (node (ref "C6") (pin "2") (pinfunction "P$2_2") (pintype "passive"))
      (node (ref "C7") (pin "2") (pinfunction "P$2_2") (pintype "passive"))
      (node (ref "C8") (pin "2") (pinfunction "P$2_2") (pintype "passive"))
      (node (ref "C9") (pin "2") (pinfunction "P$2_2") (pintype "passive"))
      (node (ref "D10") (pin "C") (pinfunction "C_C") (pintype "passive"))
      (node (ref "D12") (pin "C") (pinfunction "C_C") (pintype "passive"))
      (node (ref "D3") (pin "A") (pinfunction "A_A") (pintype "bidirectional"))
      (node (ref "D4") (pin "A") (pinfunction "A_A") (pintype "bidirectional"))
      (node (ref "D5") (pin "A") (pinfunction "A_A") (pintype "bidirectional"))
      (node (ref "D6") (pin "A") (pinfunction "A_A") (pintype "bidirectional"))
      (node (ref "D7") (pin "C") (pinfunction "C_C") (pintype "passive"))
      (node (ref "D8") (pin "C") (pinfunction "C_C") (pintype "passive"))
      (node (ref "D9") (pin "C") (pinfunction "C_C") (pintype "passive"))
      (node (ref "J1") (pin "P$5") (pinfunction "5_P$5") (pintype "passive"))
      (node (ref "J2") (pin "P$5") (pinfunction "5_P$5") (pintype "passive"))
      (node (ref "J3") (pin "P$5") (pinfunction "P$5_P$5") (pintype "bidirectional"))
      (node (ref "J4") (pin "P$9") (pinfunction "P$9_P$9") (pintype "bidirectional"))
      (node (ref "J5") (pin "P$5") (pinfunction "P$5_P$5") (pintype "bidirectional"))
      (node (ref "J5") (pin "P$6") (pinfunction "P$6_P$6") (pintype "bidirectional"))
      (node (ref "J6") (pin "P$16") (pinfunction "P$16_P$16") (pintype "bidirectional"))
      (node (ref "J6") (pin "P$5") (pinfunction "P$5_P$5") (pintype "bidirectional"))
      (node (ref "J7") (pin "P$5") (pinfunction "P$5_P$5") (pintype "bidirectional"))
      (node (ref "J8") (pin "P$2") (pinfunction "2_P$2") (pintype "bidirectional"))
      (node (ref "J8") (pin "P$9") (pinfunction "9_P$9") (pintype "bidirectional"))
      (node (ref "J9") (pin "P2") (pinfunction "2_P2") (pintype "bidirectional"))
      (node (ref "J9") (pin "P3") (pinfunction "3_P3") (pintype "bidirectional"))
      (node (ref "M1") (pin "P$1") (pinfunction "S_P$1") (pintype "bidirectional"))
      (node (ref "M1") (pin "P$2") (pinfunction "S_P$2") (pintype "bidirectional"))
      (node (ref "M1") (pin "P$3") (pinfunction "S_P$3") (pintype "bidirectional"))
      (node (ref "R11") (pin "1") (pinfunction "1_1") (pintype "passive"))
      (node (ref "R13") (pin "1") (pinfunction "1_1") (pintype "passive"))
      (node (ref "R17") (pin "1") (pinfunction "1_1") (pintype "passive"))
      (node (ref "R19") (pin "1") (pinfunction "1_1") (pintype "passive"))
      (node (ref "R21") (pin "2") (pinfunction "2_2") (pintype "passive"))
      (node (ref "R28") (pin "1") (pinfunction "1_1") (pintype "passive"))
      (node (ref "R29") (pin "1") (pinfunction "1_1") (pintype "passive"))
      (node (ref "R32") (pin "1") (pinfunction "1_1") (pintype "passive"))
      (node (ref "R33") (pin "1") (pinfunction "1_1") (pintype "passive"))
      (node (ref "R41") (pin "1") (pinfunction "1_1") (pintype "passive"))
      (node (ref "R43") (pin "1") (pinfunction "1_1") (pintype "passive"))
      (node (ref "R44") (pin "1") (pinfunction "1_1") (pintype "passive"))
      (node (ref "R47") (pin "1") (pinfunction "1_1") (pintype "passive"))
      (node (ref "R49") (pin "1") (pinfunction "1_1") (pintype "passive"))
      (node (ref "R52") (pin "1") (pinfunction "1_1") (pintype "passive"))
      (node (ref "R6") (pin "1") (pinfunction "1_1") (pintype "passive"))
      (node (ref "U1") (pin "P4") (pinfunction "GND_P4") (pintype "bidirectional"))
      (node (ref "U1") (pin "P9") (pinfunction "GND_P9") (pintype "bidirectional"))
      (node (ref "U10") (pin "P$2") (pinfunction "V-_P$2") (pintype "bidirectional"))
      (node (ref "U11") (pin "P$4") (pinfunction "V-_P$4") (pintype "bidirectional"))
      (node (ref "U12") (pin "P$3") (pinfunction "PGND_P$3") (pintype "input"))
      (node (ref "U12") (pin "P$9") (pinfunction "GND_P$9") (pintype "input"))
      (node (ref "U12") (pin "PAD") (pinfunction "GND_PAD") (pintype "input"))
      (node (ref "U13") (pin "P$3") (pinfunction "PGND_P$3") (pintype "input"))
      (node (ref "U13") (pin "P$9") (pinfunction "GND_P$9") (pintype "input"))
      (node (ref "U13") (pin "PAD") (pinfunction "GND_PAD") (pintype "input"))
      (node (ref "U14") (pin "11") (pinfunction "FSYNC_11") (pintype "bidirectional"))
      (node (ref "U14") (pin "18") (pinfunction "GND_18") (pintype "bidirectional"))
      (node (ref "U14") (pin "20") (pinfunction "RESV_20") (pintype "bidirectional"))
      (node (ref "U15") (pin "11") (pinfunction "GND_11") (pintype "bidirectional"))
      (node (ref "U15") (pin "9") (pinfunction "GND_9") (pintype "bidirectional"))
      (node (ref "U2") (pin "P$4") (pinfunction "VSS_P$4") (pintype "bidirectional"))
      (node (ref "U3") (pin "P$3") (pinfunction "GND_P$3") (pintype "bidirectional"))
      (node (ref "U4") (pin "P$3") (pinfunction "GND_P$3") (pintype "bidirectional"))
      (node (ref "U5") (pin "P$1") (pinfunction "GND_P$1") (pintype "bidirectional"))
      (node (ref "U6") (pin "P4") (pinfunction "GND_P4") (pintype "bidirectional"))
      (node (ref "U6") (pin "P9") (pinfunction "GND_P9") (pintype "bidirectional"))
      (node (ref "U7") (pin "P$7") (pinfunction "GND_P$7") (pintype "bidirectional"))
      (node (ref "U8") (pin "P$10") (pinfunction "VEE_P$10") (pintype "bidirectional"))
      (node (ref "U8") (pin "P$11") (pinfunction "GND_P$11") (pintype "bidirectional"))
      (node (ref "U9") (pin "P$10") (pinfunction "VEE_P$10") (pintype "bidirectional"))
      (node (ref "U9") (pin "P$11") (pinfunction "GND_P$11") (pintype "bidirectional"))
      (node (ref "UC1") (pin "P$22") (pinfunction "GND_P$22") (pintype "power_in"))
      (node (ref "UC1") (pin "P$33") (pinfunction "GND_P$33") (pintype "power_in"))
      (node (ref "UC1") (pin "P$47") (pinfunction "GND_P$47") (pintype "power_in"))
      (node (ref "UC1") (pin "P$54") (pinfunction "GND_P$54") (pintype "power_in"))
      (node (ref "UC1") (pin "P$7") (pinfunction "GNDANA_P$7") (pintype "power_in"))
      (node (ref "V10") (pin "P$1") (pinfunction "P$1_P$1") (pintype "bidirectional"))
      (node (ref "V11") (pin "P$1") (pinfunction "P$1_P$1") (pintype "bidirectional"))
      (node (ref "V12") (pin "P$1") (pinfunction "P$1_P$1") (pintype "bidirectional"))
      (node (ref "V9") (pin "P$1") (pinfunction "P$1_P$1") (pintype "bidirectional"))
    )
    (net (code "18") (name "IRVDD") (class "Default")
      (node (ref "J1") (pin "P$4") (pinfunction "4_P$4") (pintype "passive"))
      (node (ref "J2") (pin "P$4") (pinfunction "4_P$4") (pintype "passive"))
      (node (ref "J3") (pin "P$4") (pinfunction "P$4_P$4") (pintype "bidirectional"))
      (node (ref "J4") (pin "P$6") (pinfunction "P$6_P$6") (pintype "bidirectional"))
      (node (ref "J5") (pin "P$2") (pinfunction "P$2_P$2") (pintype "bidirectional"))
      (node (ref "J6") (pin "P$18") (pinfunction "P$18_P$18") (pintype "bidirectional"))
      (node (ref "M2") (pin "5") (pinfunction "D_5") (pintype "passive"))
      (node (ref "M2") (pin "6") (pinfunction "D_6") (pintype "passive"))
      (node (ref "M2") (pin "7") (pinfunction "D_7") (pintype "passive"))
      (node (ref "M2") (pin "8") (pinfunction "D_8") (pintype "passive"))
      (node (ref "R53") (pin "2") (pinfunction "2_2") (pintype "passive"))
    )
    (net (code "19") (name "IR_PWR_CMD") (class "Default")
      (node (ref "M1") (pin "P$4") (pinfunction "G_P$4") (pintype "bidirectional"))
      (node (ref "R21") (pin "1") (pinfunction "1_1") (pintype "passive"))
      (node (ref "UC1") (pin "P$40") (pinfunction "PB17_P$40") (pintype "bidirectional"))
    )
    (net (code "20") (name "L1_DISG") (class "Default")
      (node (ref "J7") (pin "P$18") (pinfunction "P$18_P$18") (pintype "bidirectional"))
      (node (ref "UC1") (pin "P$60") (pinfunction "PB31_P$60") (pintype "bidirectional"))
    )
    (net (code "21") (name "L1_REF") (class "Default")
      (node (ref "J7") (pin "P$20") (pinfunction "P$20_P$20") (pintype "bidirectional"))
      (node (ref "UC1") (pin "P$4") (pinfunction "PA03_P$4") (pintype "bidirectional"))
    )
    (net (code "22") (name "L1_RUN_CHG") (class "Default")
      (node (ref "J7") (pin "P$17") (pinfunction "P$17_P$17") (pintype "bidirectional"))
      (node (ref "UC1") (pin "P$2") (pinfunction "PA01_P$2") (pintype "bidirectional"))
    )
    (net (code "23") (name "L1_TEMP") (class "Default")
      (node (ref "J7") (pin "P$1") (pinfunction "P$1_P$1") (pintype "bidirectional"))
      (node (ref "U8") (pin "P$4") (pinfunction "S3_P$4") (pintype "bidirectional"))
    )
    (net (code "24") (name "L2_DISG") (class "Default")
      (node (ref "J7") (pin "P$19") (pinfunction "P$19_P$19") (pintype "bidirectional"))
      (node (ref "UC1") (pin "P$1") (pinfunction "PA00_P$1") (pintype "bidirectional"))
    )
    (net (code "25") (name "L2_REF") (class "Default")
      (node (ref "J7") (pin "P$8") (pinfunction "P$8_P$8") (pintype "bidirectional"))
      (node (ref "UC1") (pin "P$16") (pinfunction "PA07_P$16") (pintype "bidirectional"))
    )
    (net (code "26") (name "L2_RUN_CHG") (class "Default")
      (node (ref "J7") (pin "P$16") (pinfunction "P$16_P$16") (pintype "bidirectional"))
      (node (ref "UC1") (pin "P$5") (pinfunction "PB04_P$5") (pintype "bidirectional"))
    )
    (net (code "27") (name "L2_TEMP") (class "Default")
      (node (ref "J7") (pin "P$2") (pinfunction "P$2_P$2") (pintype "bidirectional"))
      (node (ref "U8") (pin "P$3") (pinfunction "S2_P$3") (pintype "bidirectional"))
    )
    (net (code "28") (name "LED1SNS") (class "Default")
      (node (ref "J6") (pin "P$15") (pinfunction "P$15_P$15") (pintype "bidirectional"))
      (node (ref "UC1") (pin "P$64") (pinfunction "PB03_P$64") (pintype "bidirectional"))
    )
    (net (code "29") (name "LED1TEMP") (class "Default")
      (node (ref "J6") (pin "P$1") (pinfunction "P$1_P$1") (pintype "bidirectional"))
      (node (ref "U8") (pin "P$8") (pinfunction "S7_P$8") (pintype "bidirectional"))
    )
    (net (code "30") (name "LED2SNS") (class "Default")
      (node (ref "J6") (pin "P$14") (pinfunction "P$14_P$14") (pintype "bidirectional"))
      (node (ref "UC1") (pin "P$63") (pinfunction "PB02_P$63") (pintype "bidirectional"))
    )
    (net (code "31") (name "LED2TEMP") (class "Default")
      (node (ref "J6") (pin "P$2") (pinfunction "P$2_P$2") (pintype "bidirectional"))
      (node (ref "U8") (pin "P$7") (pinfunction "S6_P$7") (pintype "bidirectional"))
    )
    (net (code "32") (name "LED3SNS") (class "Default")
      (node (ref "J6") (pin "P$13") (pinfunction "P$13_P$13") (pintype "bidirectional"))
      (node (ref "UC1") (pin "P$62") (pinfunction "PB01_P$62") (pintype "bidirectional"))
    )
    (net (code "33") (name "LED3TEMP") (class "Default")
      (node (ref "J6") (pin "P$3") (pinfunction "P$3_P$3") (pintype "bidirectional"))
      (node (ref "U8") (pin "P$6") (pinfunction "S5_P$6") (pintype "bidirectional"))
    )
    (net (code "34") (name "LED4SNS") (class "Default")
      (node (ref "J6") (pin "P$12") (pinfunction "P$12_P$12") (pintype "bidirectional"))
      (node (ref "UC1") (pin "P$61") (pinfunction "PB00_P$61") (pintype "bidirectional"))
    )
    (net (code "35") (name "LED4TEMP") (class "Default")
      (node (ref "J6") (pin "P$4") (pinfunction "P$4_P$4") (pintype "bidirectional"))
      (node (ref "U8") (pin "P$5") (pinfunction "S4_P$5") (pintype "bidirectional"))
    )
    (net (code "36") (name "LED_SHDN") (class "Default")
      (node (ref "J6") (pin "P$11") (pinfunction "P$11_P$11") (pintype "bidirectional"))
      (node (ref "R58") (pin "1") (pinfunction "1_1") (pintype "passive"))
      (node (ref "U5") (pin "P$3") (pinfunction "OUT_P$3") (pintype "bidirectional"))
    )
    (net (code "37") (name "LF1REF") (class "Default")
      (node (ref "J7") (pin "P$25") (pinfunction "P$25_P$25") (pintype "bidirectional"))
      (node (ref "UC1") (pin "P$15") (pinfunction "PA06_P$15") (pintype "bidirectional"))
    )
    (net (code "38") (name "LF1_TEMP") (class "Default")
      (node (ref "J7") (pin "P$3") (pinfunction "P$3_P$3") (pintype "bidirectional"))
      (node (ref "U8") (pin "P$2") (pinfunction "S1_P$2") (pintype "bidirectional"))
    )
    (net (code "39") (name "LF2REF") (class "Default")
      (node (ref "J7") (pin "P$12") (pinfunction "P$12_P$12") (pintype "bidirectional"))
      (node (ref "UC1") (pin "P$14") (pinfunction "PA05_P$14") (pintype "bidirectional"))
    )
    (net (code "40") (name "LF3REF") (class "Default")
      (node (ref "J7") (pin "P$13") (pinfunction "P$13_P$13") (pintype "bidirectional"))
      (node (ref "UC1") (pin "P$12") (pinfunction "PB09_P$12") (pintype "bidirectional"))
    )
    (net (code "41") (name "LF3_TEMP") (class "Default")
      (node (ref "J7") (pin "P$4") (pinfunction "P$4_P$4") (pintype "bidirectional"))
      (node (ref "U8") (pin "P$1") (pinfunction "S0_P$1") (pintype "bidirectional"))
    )
    (net (code "42") (name "LF4REF") (class "Default")
      (node (ref "J7") (pin "P$24") (pinfunction "P$24_P$24") (pintype "bidirectional"))
      (node (ref "UC1") (pin "P$13") (pinfunction "PA04_P$13") (pintype "bidirectional"))
    )
    (net (code "43") (name "LFB1OSNS") (class "Default")
      (node (ref "J7") (pin "P$9") (pinfunction "P$9_P$9") (pintype "bidirectional"))
      (node (ref "UC1") (pin "P$20") (pinfunction "PA11_P$20") (pintype "bidirectional"))
    )
    (net (code "44") (name "LFB1SNS") (class "Default")
      (node (ref "J7") (pin "P$10") (pinfunction "P$10_P$10") (pintype "bidirectional"))
      (node (ref "UC1") (pin "P$19") (pinfunction "PA10_P$19") (pintype "bidirectional"))
    )
    (net (code "45") (name "LFB2OSNS") (class "Default")
      (node (ref "J7") (pin "P$27") (pinfunction "P$27_P$27") (pintype "bidirectional"))
      (node (ref "UC1") (pin "P$18") (pinfunction "PA09_P$18") (pintype "bidirectional"))
    )
    (net (code "46") (name "LFB2SNS") (class "Default")
      (node (ref "J7") (pin "P$26") (pinfunction "P$26_P$26") (pintype "bidirectional"))
      (node (ref "UC1") (pin "P$17") (pinfunction "PA08_P$17") (pintype "bidirectional"))
    )
    (net (code "47") (name "LF_B1_OUTEN") (class "Default")
      (node (ref "J7") (pin "P$15") (pinfunction "P$15_P$15") (pintype "bidirectional"))
      (node (ref "UC1") (pin "P$9") (pinfunction "PB06_P$9") (pintype "bidirectional"))
    )
    (net (code "48") (name "LF_B1_RUNCHG") (class "Default")
      (node (ref "J7") (pin "P$21") (pinfunction "P$21_P$21") (pintype "bidirectional"))
      (node (ref "UC1") (pin "P$6") (pinfunction "PB05_P$6") (pintype "bidirectional"))
    )
    (net (code "49") (name "LF_B2_OUTEN") (class "Default")
      (node (ref "J7") (pin "P$14") (pinfunction "P$14_P$14") (pintype "bidirectional"))
      (node (ref "UC1") (pin "P$10") (pinfunction "PB07_P$10") (pintype "bidirectional"))
    )
    (net (code "50") (name "LF_B2_RUNCHG") (class "Default")
      (node (ref "J7") (pin "P$11") (pinfunction "P$11_P$11") (pintype "bidirectional"))
      (node (ref "UC1") (pin "P$23") (pinfunction "PB10_P$23") (pintype "bidirectional"))
    )
    (net (code "51") (name "Net-(C1-P$1)") (class "Default")
      (node (ref "C1") (pin "1") (pinfunction "P$1_1") (pintype "passive"))
      (node (ref "UC1") (pin "P$55") (pinfunction "VDDCORE_P$55") (pintype "power_in"))
    )
    (net (code "52") (name "Net-(C6-P$1)") (class "Default")
      (node (ref "C6") (pin "1") (pinfunction "P$1_1") (pintype "passive"))
      (node (ref "C8") (pin "1") (pinfunction "P$1_1") (pintype "passive"))
      (node (ref "L1") (pin "2") (pinfunction "P$2_2") (pintype "passive"))
      (node (ref "UC1") (pin "P$8") (pinfunction "VDDANA_P$8") (pintype "power_in"))
    )
    (net (code "53") (name "Net-(C14-P$1)") (class "Default")
      (node (ref "C14") (pin "1") (pinfunction "P$1_1") (pintype "passive"))
      (node (ref "R9") (pin "1") (pinfunction "1_1") (pintype "passive"))
      (node (ref "U12") (pin "P$6") (pinfunction "EN_P$6") (pintype "input"))
      (node (ref "U12") (pin "P$7") (pinfunction "PS/SYNC_P$7") (pintype "input"))
      (node (ref "U12") (pin "P$8") (pinfunction "VINA_P$8") (pintype "input"))
    )
    (net (code "54") (name "Net-(C15-P$1)") (class "Default")
      (node (ref "C15") (pin "1") (pinfunction "P$1_1") (pintype "passive"))
      (node (ref "R10") (pin "1") (pinfunction "1_1") (pintype "passive"))
      (node (ref "U13") (pin "P$7") (pinfunction "PS/SYNC_P$7") (pintype "input"))
      (node (ref "U13") (pin "P$8") (pinfunction "VINA_P$8") (pintype "input"))
    )
    (net (code "55") (name "Net-(C16-P$1)") (class "Default")
      (node (ref "C16") (pin "1") (pinfunction "P$1_1") (pintype "passive"))
      (node (ref "U15") (pin "10") (pinfunction "C1_10") (pintype "bidirectional"))
    )
    (net (code "56") (name "Net-(C17-P$1)") (class "Default")
      (node (ref "C17") (pin "1") (pinfunction "P$1_1") (pintype "passive"))
      (node (ref "U15") (pin "8") (pinfunction "SETP_8") (pintype "bidirectional"))
    )
    (net (code "57") (name "Net-(C17-P$2)") (class "Default")
      (node (ref "C17") (pin "2") (pinfunction "P$2_2") (pintype "passive"))
      (node (ref "U15") (pin "12") (pinfunction "SETC_12") (pintype "bidirectional"))
    )
    (net (code "58") (name "Net-(C20-P$1)") (class "Default")
      (node (ref "C20") (pin "1") (pinfunction "P$1_1") (pintype "passive"))
      (node (ref "U14") (pin "10") (pinfunction "REGOUT_10") (pintype "bidirectional"))
    )
    (net (code "59") (name "Net-(C26-P$1)") (class "Default")
      (node (ref "C26") (pin "1") (pinfunction "P$1_1") (pintype "passive"))
      (node (ref "R23") (pin "2") (pinfunction "2_2") (pintype "passive"))
      (node (ref "U5") (pin "P$6") (pinfunction "THRSH_P$6") (pintype "bidirectional"))
      (node (ref "U5") (pin "P$7") (pinfunction "DISG_P$7") (pintype "bidirectional"))
    )
    (net (code "60") (name "Net-(C27-P$1)") (class "Default")
      (node (ref "C27") (pin "1") (pinfunction "P$1_1") (pintype "passive"))
      (node (ref "U5") (pin "P$5") (pinfunction "CV_P$5") (pintype "bidirectional"))
    )
    (net (code "61") (name "Net-(D7-PadA)") (class "Default")
      (node (ref "D7") (pin "A") (pinfunction "A_A") (pintype "passive"))
      (node (ref "R53") (pin "1") (pinfunction "1_1") (pintype "passive"))
    )
    (net (code "62") (name "Net-(D8-PadA)") (class "Default")
      (node (ref "D8") (pin "A") (pinfunction "A_A") (pintype "passive"))
      (node (ref "R54") (pin "1") (pinfunction "1_1") (pintype "passive"))
    )
    (net (code "63") (name "Net-(D9-PadA)") (class "Default")
      (node (ref "D9") (pin "A") (pinfunction "A_A") (pintype "passive"))
      (node (ref "R55") (pin "1") (pinfunction "1_1") (pintype "passive"))
    )
    (net (code "64") (name "Net-(D10-PadA)") (class "Default")
      (node (ref "D10") (pin "A") (pinfunction "A_A") (pintype "passive"))
      (node (ref "R56") (pin "1") (pinfunction "1_1") (pintype "passive"))
    )
    (net (code "65") (name "Net-(D12-PadA)") (class "Default")
      (node (ref "D12") (pin "A") (pinfunction "A_A") (pintype "passive"))
      (node (ref "R58") (pin "2") (pinfunction "2_2") (pintype "passive"))
    )
    (net (code "66") (name "Net-(M2-G)") (class "Default")
      (node (ref "M1") (pin "P$5") (pinfunction "D_P$5") (pintype "bidirectional"))
      (node (ref "M1") (pin "P$6") (pinfunction "D_P$6") (pintype "bidirectional"))
      (node (ref "M1") (pin "P$7") (pinfunction "D_P$7") (pintype "bidirectional"))
      (node (ref "M1") (pin "P$8") (pinfunction "D_P$8") (pintype "bidirectional"))
      (node (ref "M1") (pin "PAD") (pinfunction "D_PAD") (pintype "bidirectional"))
      (node (ref "M2") (pin "4") (pinfunction "G_4") (pintype "passive"))
      (node (ref "R22") (pin "1") (pinfunction "1_1") (pintype "passive"))
    )
    (net (code "67") (name "Net-(U1-~{HOLD})") (class "Default")
      (node (ref "R1") (pin "1") (pinfunction "1_1") (pintype "passive"))
      (node (ref "U1") (pin "P7") (pinfunction "~{HOLD}_P7") (pintype "bidirectional"))
    )
    (net (code "68") (name "Net-(U1-~{WP})") (class "Default")
      (node (ref "R3") (pin "1") (pinfunction "1_1") (pintype "passive"))
      (node (ref "U1") (pin "P3") (pinfunction "~{WP}_P3") (pintype "bidirectional"))
    )
    (net (code "69") (name "Net-(U2-E2)") (class "Default")
      (node (ref "R17") (pin "2") (pinfunction "2_2") (pintype "passive"))
      (node (ref "R18") (pin "1") (pinfunction "1_1") (pintype "passive"))
      (node (ref "U2") (pin "P$3") (pinfunction "E2_P$3") (pintype "bidirectional"))
    )
    (net (code "70") (name "Net-(U2-~{WC})") (class "Default")
      (node (ref "R19") (pin "2") (pinfunction "2_2") (pintype "passive"))
      (node (ref "U2") (pin "P$7") (pinfunction "~{WC}_P$7") (pintype "bidirectional"))
    )
    (net (code "71") (name "Net-(U6-~{HOLD})") (class "Default")
      (node (ref "R14") (pin "1") (pinfunction "1_1") (pintype "passive"))
      (node (ref "U6") (pin "P7") (pinfunction "~{HOLD}_P7") (pintype "bidirectional"))
    )
    (net (code "72") (name "Net-(U6-~{WP})") (class "Default")
      (node (ref "R16") (pin "1") (pinfunction "1_1") (pintype "passive"))
      (node (ref "U6") (pin "P3") (pinfunction "~{WP}_P3") (pintype "bidirectional"))
    )
    (net (code "73") (name "Net-(U10-+)") (class "Default")
      (node (ref "R34") (pin "2") (pinfunction "2_2") (pintype "passive"))
      (node (ref "U10") (pin "P$3") (pinfunction "+_P$3") (pintype "bidirectional"))
    )
    (net (code "74") (name "Net-(U10--)") (class "Default")
      (node (ref "R37") (pin "2") (pinfunction "2_2") (pintype "passive"))
      (node (ref "U10") (pin "P$4") (pinfunction "-_P$4") (pintype "bidirectional"))
    )
    (net (code "75") (name "Net-(U10-OUT)") (class "Default")
      (node (ref "R36") (pin "2") (pinfunction "2_2") (pintype "passive"))
      (node (ref "R37") (pin "1") (pinfunction "1_1") (pintype "passive"))
      (node (ref "U10") (pin "P$1") (pinfunction "OUT_P$1") (pintype "bidirectional"))
    )
    (net (code "76") (name "Net-(U11-A+)") (class "Default")
      (node (ref "R42") (pin "1") (pinfunction "1_1") (pintype "passive"))
      (node (ref "R43") (pin "2") (pinfunction "2_2") (pintype "passive"))
      (node (ref "U11") (pin "P$3") (pinfunction "A+_P$3") (pintype "bidirectional"))
    )
    (net (code "77") (name "Net-(U11-B+)") (class "Default")
      (node (ref "D2") (pin "A") (pinfunction "A_A") (pintype "bidirectional"))
      (node (ref "U11") (pin "P$1") (pinfunction "OUTA_P$1") (pintype "bidirectional"))
      (node (ref "U11") (pin "P$5") (pinfunction "B+_P$5") (pintype "bidirectional"))
    )
    (net (code "78") (name "Net-(U11-B-)") (class "Default")
      (node (ref "R44") (pin "2") (pinfunction "2_2") (pintype "passive"))
      (node (ref "R45") (pin "2") (pinfunction "2_2") (pintype "passive"))
      (node (ref "U11") (pin "P$6") (pinfunction "B-_P$6") (pintype "bidirectional"))
    )
    (net (code "79") (name "Net-(U12-L1)") (class "Default")
      (node (ref "L2") (pin "1") (pinfunction "1_1") (pintype "passive"))
      (node (ref "U12") (pin "P$4") (pinfunction "L1_P$4") (pintype "input"))
    )
    (net (code "80") (name "Net-(U12-L2)") (class "Default")
      (node (ref "L2") (pin "2") (pinfunction "2_2") (pintype "passive"))
      (node (ref "U12") (pin "P$2") (pinfunction "L2_P$2") (pintype "input"))
    )
    (net (code "81") (name "Net-(U13-L1)") (class "Default")
      (node (ref "L3") (pin "1") (pinfunction "1_1") (pintype "passive"))
      (node (ref "U13") (pin "P$4") (pinfunction "L1_P$4") (pintype "input"))
    )
    (net (code "82") (name "Net-(U13-L2)") (class "Default")
      (node (ref "L3") (pin "2") (pinfunction "2_2") (pintype "passive"))
      (node (ref "U13") (pin "P$2") (pinfunction "L2_P$2") (pintype "input"))
    )
    (net (code "83") (name "PD_FLASH") (class "Default")
      (node (ref "J6") (pin "P$10") (pinfunction "P$10_P$10") (pintype "bidirectional"))
      (node (ref "U9") (pin "P$4") (pinfunction "S3_P$4") (pintype "bidirectional"))
    )
    (net (code "84") (name "PD_IN") (class "Default")
      (node (ref "D2") (pin "C") (pinfunction "C_C") (pintype "bidirectional"))
      (node (ref "U11") (pin "P$2") (pinfunction "A-_P$2") (pintype "bidirectional"))
      (node (ref "U9") (pin "P$9") (pinfunction "DO_P$9") (pintype "bidirectional"))
    )
    (net (code "85") (name "PD_OUT") (class "Default")
      (node (ref "R45") (pin "1") (pinfunction "1_1") (pintype "passive"))
      (node (ref "U11") (pin "P$7") (pinfunction "OUTB_P$7") (pintype "bidirectional"))
      (node (ref "UC1") (pin "P$3") (pinfunction "PA02_P$3") (pintype "bidirectional"))
    )
    (net (code "86") (name "PD_XN") (class "Default")
      (node (ref "J2") (pin "P$1") (pinfunction "1_P$1") (pintype "passive"))
      (node (ref "U9") (pin "P$2") (pinfunction "S1_P$2") (pintype "bidirectional"))
    )
    (net (code "87") (name "PD_XP") (class "Default")
      (node (ref "J5") (pin "P$1") (pinfunction "P$1_P$1") (pintype "bidirectional"))
      (node (ref "U9") (pin "P$6") (pinfunction "S5_P$6") (pintype "bidirectional"))
    )
    (net (code "88") (name "PD_YN") (class "Default")
      (node (ref "J1") (pin "P$1") (pinfunction "1_P$1") (pintype "passive"))
      (node (ref "U9") (pin "P$3") (pinfunction "S2_P$3") (pintype "bidirectional"))
    )
    (net (code "89") (name "PD_ZN") (class "Default")
      (node (ref "J4") (pin "P$5") (pinfunction "P$5_P$5") (pintype "bidirectional"))
      (node (ref "U9") (pin "P$5") (pinfunction "S4_P$5") (pintype "bidirectional"))
    )
    (net (code "90") (name "PD_ZP") (class "Default")
      (node (ref "J3") (pin "P$1") (pinfunction "P$1_P$1") (pintype "bidirectional"))
      (node (ref "U9") (pin "P$1") (pinfunction "S0_P$1") (pintype "bidirectional"))
    )
    (net (code "91") (name "RAD_PWR_RUN") (class "Default")
      (node (ref "J8") (pin "P$7") (pinfunction "7_P$7") (pintype "bidirectional"))
      (node (ref "UC1") (pin "P$41") (pinfunction "PA20_P$41") (pintype "bidirectional"))
    )
    (net (code "92") (name "RX_DATA") (class "Default")
      (node (ref "R20") (pin "1") (pinfunction "1_1") (pintype "passive"))
      (node (ref "U3") (pin "P$4") (pinfunction "Y_P$4") (pintype "bidirectional"))
      (node (ref "UC1") (pin "P$46") (pinfunction "PA25_P$46") (pintype "bidirectional"))
      (node (ref "V1") (pin "P$1") (pinfunction "P$1_P$1") (pintype "bidirectional"))
    )
    (net (code "93") (name "RX_EN") (class "Default")
      (node (ref "U3") (pin "P$1") (pinfunction "~{OE}_P$1") (pintype "bidirectional"))
      (node (ref "UC1") (pin "P$43") (pinfunction "PA22_P$43") (pintype "bidirectional"))
    )
    (net (code "94") (name "RX_IN") (class "Default")
      (node (ref "J8") (pin "P$4") (pinfunction "4_P$4") (pintype "bidirectional"))
      (node (ref "R20") (pin "2") (pinfunction "2_2") (pintype "passive"))
      (node (ref "U3") (pin "P$2") (pinfunction "A_P$2") (pintype "bidirectional"))
    )
    (net (code "95") (name "SCK") (class "Default")
      (node (ref "R6") (pin "2") (pinfunction "2_2") (pintype "passive"))
      (node (ref "U1") (pin "P6") (pinfunction "SCK_P6") (pintype "bidirectional"))
      (node (ref "U6") (pin "P6") (pinfunction "SCK_P6") (pintype "bidirectional"))
      (node (ref "UC1") (pin "P$38") (pinfunction "PA19_P$38") (pintype "bidirectional"))
    )
    (net (code "96") (name "SCL") (class "Default")
      (node (ref "J1") (pin "P$2") (pinfunction "2_P$2") (pintype "passive"))
      (node (ref "J2") (pin "P$2") (pinfunction "2_P$2") (pintype "passive"))
      (node (ref "J3") (pin "P$3") (pinfunction "P$3_P$3") (pintype "bidirectional"))
      (node (ref "J4") (pin "P$4") (pinfunction "P$4_P$4") (pintype "bidirectional"))
      (node (ref "J5") (pin "P$4") (pinfunction "P$4_P$4") (pintype "bidirectional"))
      (node (ref "J6") (pin "P$20") (pinfunction "P$20_P$20") (pintype "bidirectional"))
      (node (ref "J7") (pin "P$23") (pinfunction "P$23_P$23") (pintype "bidirectional"))
      (node (ref "R7") (pin "1") (pinfunction "1_1") (pintype "passive"))
      (node (ref "U14") (pin "23") (pinfunction "SCL_23") (pintype "bidirectional"))
      (node (ref "U15") (pin "1") (pinfunction "SCL_1") (pintype "bidirectional"))
      (node (ref "U2") (pin "P$6") (pinfunction "SCL_P$6") (pintype "bidirectional"))
      (node (ref "U7") (pin "P$1") (pinfunction "SCL_P$1") (pintype "bidirectional"))
      (node (ref "U8") (pin "P$15") (pinfunction "SCL_P$15") (pintype "bidirectional"))
      (node (ref "U9") (pin "P$15") (pinfunction "SCL_P$15") (pintype "bidirectional"))
      (node (ref "UC1") (pin "P$26") (pinfunction "PB13_P$26") (pintype "bidirectional"))
      (node (ref "V5") (pin "P$1") (pinfunction "P$1_P$1") (pintype "bidirectional"))
    )
    (net (code "97") (name "SDA") (class "Default")
      (node (ref "J1") (pin "P$3") (pinfunction "3_P$3") (pintype "passive"))
      (node (ref "J2") (pin "P$3") (pinfunction "3_P$3") (pintype "passive"))
      (node (ref "J3") (pin "P$2") (pinfunction "P$2_P$2") (pintype "bidirectional"))
      (node (ref "J4") (pin "P$3") (pinfunction "P$3_P$3") (pintype "bidirectional"))
      (node (ref "J5") (pin "P$3") (pinfunction "P$3_P$3") (pintype "bidirectional"))
      (node (ref "J6") (pin "P$19") (pinfunction "P$19_P$19") (pintype "bidirectional"))
      (node (ref "J7") (pin "P$22") (pinfunction "P$22_P$22") (pintype "bidirectional"))
      (node (ref "R8") (pin "1") (pinfunction "1_1") (pintype "passive"))
      (node (ref "U14") (pin "24") (pinfunction "SDA_24") (pintype "bidirectional"))
      (node (ref "U15") (pin "16") (pinfunction "SDA_16") (pintype "bidirectional"))
      (node (ref "U2") (pin "P$5") (pinfunction "SDA_P$5") (pintype "bidirectional"))
      (node (ref "U7") (pin "P$2") (pinfunction "SDA_P$2") (pintype "bidirectional"))
      (node (ref "U8") (pin "P$14") (pinfunction "SDA_P$14") (pintype "bidirectional"))
      (node (ref "U9") (pin "P$14") (pinfunction "SDA_P$14") (pintype "bidirectional"))
      (node (ref "UC1") (pin "P$25") (pinfunction "PB12_P$25") (pintype "bidirectional"))
      (node (ref "V4") (pin "P$1") (pinfunction "P$1_P$1") (pintype "bidirectional"))
    )
    (net (code "98") (name "SI") (class "Default")
      (node (ref "R5") (pin "1") (pinfunction "1_1") (pintype "passive"))
      (node (ref "U1") (pin "P5") (pinfunction "SI_P5") (pintype "bidirectional"))
      (node (ref "U6") (pin "P5") (pinfunction "SI_P5") (pintype "bidirectional"))
      (node (ref "UC1") (pin "P$37") (pinfunction "PA18_P$37") (pintype "bidirectional"))
    )
    (net (code "99") (name "SO") (class "Default")
      (node (ref "R4") (pin "1") (pinfunction "1_1") (pintype "passive"))
      (node (ref "U1") (pin "P2") (pinfunction "SO_P2") (pintype "bidirectional"))
      (node (ref "U6") (pin "P2") (pinfunction "SO_P2") (pintype "bidirectional"))
      (node (ref "UC1") (pin "P$35") (pinfunction "PA16_P$35") (pintype "bidirectional"))
    )
    (net (code "100") (name "SWDCLK") (class "Default")
      (node (ref "J4") (pin "P$7") (pinfunction "P$7_P$7") (pintype "bidirectional"))
      (node (ref "J9") (pin "P9") (pinfunction "9_P9") (pintype "bidirectional"))
      (node (ref "UC1") (pin "P$57") (pinfunction "PA30_P$57") (pintype "bidirectional"))
    )
    (net (code "101") (name "SWDIO") (class "Default")
      (node (ref "J4") (pin "P$8") (pinfunction "P$8_P$8") (pintype "bidirectional"))
      (node (ref "J9") (pin "P10") (pinfunction "10_P10") (pintype "bidirectional"))
      (node (ref "UC1") (pin "P$58") (pinfunction "PA31_P$58") (pintype "bidirectional"))
    )
    (net (code "102") (name "TEMP_IN") (class "Default")
      (node (ref "R34") (pin "1") (pinfunction "1_1") (pintype "passive"))
      (node (ref "R41") (pin "2") (pinfunction "2_2") (pintype "passive"))
      (node (ref "U8") (pin "P$9") (pinfunction "DO_P$9") (pintype "bidirectional"))
    )
    (net (code "103") (name "TEMP_OUT") (class "Default")
      (node (ref "R36") (pin "1") (pinfunction "1_1") (pintype "passive"))
      (node (ref "UC1") (pin "P$11") (pinfunction "PB08_P$11") (pintype "bidirectional"))
    )
    (net (code "104") (name "TRIG") (class "Default")
      (node (ref "C28") (pin "2") (pinfunction "P$2_2") (pintype "passive"))
      (node (ref "D1") (pin "A") (pinfunction "A_A") (pintype "bidirectional"))
      (node (ref "R24") (pin "2") (pinfunction "2_2") (pintype "passive"))
      (node (ref "U5") (pin "P$2") (pinfunction "TRIG_P$2") (pintype "bidirectional"))
    )
    (net (code "105") (name "TX_DATA") (class "Default")
      (node (ref "U4") (pin "P$2") (pinfunction "A_P$2") (pintype "bidirectional"))
      (node (ref "UC1") (pin "P$45") (pinfunction "PA24_P$45") (pintype "bidirectional"))
      (node (ref "V2") (pin "P$1") (pinfunction "P$1_P$1") (pintype "bidirectional"))
    )
    (net (code "106") (name "TX_EN") (class "Default")
      (node (ref "U4") (pin "P$1") (pinfunction "~{OE}_P$1") (pintype "bidirectional"))
      (node (ref "UC1") (pin "P$44") (pinfunction "PA23_P$44") (pintype "bidirectional"))
    )
    (net (code "107") (name "TX_OUT") (class "Default")
      (node (ref "J8") (pin "P$6") (pinfunction "6_P$6") (pintype "bidirectional"))
      (node (ref "U4") (pin "P$4") (pinfunction "Y_P$4") (pintype "bidirectional"))
    )
    (net (code "108") (name "VIN") (class "Default")
      (node (ref "C10") (pin "1") (pinfunction "P$1_1") (pintype "passive"))
      (node (ref "C11") (pin "1") (pinfunction "P$1_1") (pintype "passive"))
      (node (ref "J8") (pin "P$1") (pinfunction "1_P$1") (pintype "bidirectional"))
      (node (ref "J8") (pin "P$10") (pinfunction "10_P$10") (pintype "bidirectional"))
      (node (ref "R10") (pin "2") (pinfunction "2_2") (pintype "passive"))
      (node (ref "R50") (pin "P$1") (pinfunction "1_P$1") (pintype "passive"))
      (node (ref "R51") (pin "P$2") (pinfunction "2_P$2") (pintype "passive"))
      (node (ref "R52") (pin "2") (pinfunction "2_2") (pintype "passive"))
      (node (ref "R9") (pin "2") (pinfunction "2_2") (pintype "passive"))
      (node (ref "U12") (pin "P$5") (pinfunction "VIN_P$5") (pintype "input"))
      (node (ref "U13") (pin "P$5") (pinfunction "VIN_P$5") (pintype "input"))
      (node (ref "V3") (pin "P$1") (pinfunction "P$1_P$1") (pintype "bidirectional"))
    )
    (net (code "109") (name "VIN-EXT") (class "Default")
      (node (ref "D4") (pin "C") (pinfunction "C_C") (pintype "bidirectional"))
      (node (ref "J4") (pin "P$1") (pinfunction "P$1_P$1") (pintype "bidirectional"))
      (node (ref "R51") (pin "P$1") (pinfunction "1_P$1") (pintype "passive"))
    )
    (net (code "110") (name "VIN-INT") (class "Default")
      (node (ref "D3") (pin "C") (pinfunction "C_C") (pintype "bidirectional"))
      (node (ref "J5") (pin "P$7") (pinfunction "P$7_P$7") (pintype "bidirectional"))
      (node (ref "J5") (pin "P$8") (pinfunction "P$8_P$8") (pintype "bidirectional"))
      (node (ref "R50") (pin "P$2") (pinfunction "2_P$2") (pintype "passive"))
    )
    (net (code "111") (name "unconnected-(J1-6-PadP$6)") (class "Default")
      (node (ref "J1") (pin "P$6") (pinfunction "6_P$6") (pintype "passive"))
    )
    (net (code "112") (name "unconnected-(J2-6-PadP$6)") (class "Default")
      (node (ref "J2") (pin "P$6") (pinfunction "6_P$6") (pintype "passive"))
    )
    (net (code "113") (name "unconnected-(J3-PadP$6)") (class "Default")
      (node (ref "J3") (pin "P$6") (pinfunction "P$6_P$6") (pintype "bidirectional"))
    )
    (net (code "114") (name "unconnected-(J9-4-PadP4)") (class "Default")
      (node (ref "J9") (pin "P4") (pinfunction "4_P4") (pintype "bidirectional"))
    )
    (net (code "115") (name "unconnected-(J9-5-PadP5)") (class "Default")
      (node (ref "J9") (pin "P5") (pinfunction "5_P5") (pintype "bidirectional"))
    )
    (net (code "116") (name "unconnected-(J9-7-PadP7)") (class "Default")
      (node (ref "J9") (pin "P7") (pinfunction "7_P7") (pintype "bidirectional"))
    )
    (net (code "117") (name "unconnected-(J9-8-PadP8)") (class "Default")
      (node (ref "J9") (pin "P8") (pinfunction "8_P8") (pintype "bidirectional"))
    )
    (net (code "118") (name "unconnected-(U9-S6-PadP$7)") (class "Default")
      (node (ref "U9") (pin "P$7") (pinfunction "S6_P$7") (pintype "bidirectional"))
    )
    (net (code "119") (name "unconnected-(U9-S7-PadP$8)") (class "Default")
      (node (ref "U9") (pin "P$8") (pinfunction "S7_P$8") (pintype "bidirectional"))
    )
    (net (code "120") (name "unconnected-(U14-AUX_CL-Pad7)") (class "Default")
      (node (ref "U14") (pin "7") (pinfunction "AUX_CL_7") (pintype "bidirectional"))
    )
    (net (code "121") (name "unconnected-(U14-AUX_DA-Pad21)") (class "Default")
      (node (ref "U14") (pin "21") (pinfunction "AUX_DA_21") (pintype "bidirectional"))
    )
    (net (code "122") (name "unconnected-(U14-INT-Pad12)") (class "Default")
      (node (ref "U14") (pin "12") (pinfunction "INT_12") (pintype "bidirectional"))
    )
    (net (code "123") (name "unconnected-(U14-NCS-Pad22)") (class "Default")
      (node (ref "U14") (pin "22") (pinfunction "NCS_22") (pintype "bidirectional"))
    )
    (net (code "124") (name "unconnected-(U14-RESV-Pad19)") (class "Default")
      (node (ref "U14") (pin "19") (pinfunction "RESV_19") (pintype "bidirectional"))
    )
    (net (code "125") (name "unconnected-(U15-DRDY-Pad15)") (class "Default")
      (node (ref "U15") (pin "15") (pinfunction "DRDY_15") (pintype "bidirectional"))
    )
    (net (code "126") (name "unconnected-(U15-NC-Pad3)") (class "Default")
      (node (ref "U15") (pin "3") (pinfunction "NC_3") (pintype "bidirectional"))
    )
    (net (code "127") (name "unconnected-(U15-NC-Pad5)") (class "Default")
      (node (ref "U15") (pin "5") (pinfunction "NC_5") (pintype "bidirectional"))
    )
    (net (code "128") (name "unconnected-(U15-NC-Pad6)") (class "Default")
      (node (ref "U15") (pin "6") (pinfunction "NC_6") (pintype "bidirectional"))
    )
    (net (code "129") (name "unconnected-(U15-NC-Pad7)") (class "Default")
      (node (ref "U15") (pin "7") (pinfunction "NC_7") (pintype "bidirectional"))
    )
    (net (code "130") (name "unconnected-(U15-NC-Pad14)") (class "Default")
      (node (ref "U15") (pin "14") (pinfunction "NC_14") (pintype "bidirectional"))
    )
    (net (code "131") (name "unconnected-(UC1-PA27-PadP$51)") (class "Default")
      (node (ref "UC1") (pin "P$51") (pinfunction "PA27_P$51") (pintype "bidirectional"))
    )
    (net (code "132") (name "unconnected-(UC1-PA28-PadP$53)") (class "Default")
      (node (ref "UC1") (pin "P$53") (pinfunction "PA28_P$53") (pintype "bidirectional"))
    )
    (net (code "133") (name "unconnected-(UC1-PB15-PadP$28)") (class "Default")
      (node (ref "UC1") (pin "P$28") (pinfunction "PB15_P$28") (pintype "bidirectional"))
    )
    (net (code "134") (name "unconnected-(UC1-PB22-PadP$49)") (class "Default")
      (node (ref "UC1") (pin "P$49") (pinfunction "PB22_P$49") (pintype "bidirectional"))
    )
    (net (code "135") (name "unconnected-(UC1-PB23-PadP$50)") (class "Default")
      (node (ref "UC1") (pin "P$50") (pinfunction "PB23_P$50") (pintype "bidirectional"))
    )
    (net (code "136") (name "unconnected-(UC1-PB30-PadP$59)") (class "Default")
      (node (ref "UC1") (pin "P$59") (pinfunction "PB30_P$59") (pintype "bidirectional"))
    )
    (net (code "137") (name "~{CS2}") (class "Default")
      (node (ref "R15") (pin "1") (pinfunction "1_1") (pintype "passive"))
      (node (ref "U6") (pin "P1") (pinfunction "~{CS}_P1") (pintype "bidirectional"))
      (node (ref "UC1") (pin "P$39") (pinfunction "PB16_P$39") (pintype "bidirectional"))
    )
    (net (code "138") (name "~{CS}") (class "Default")
      (node (ref "R2") (pin "1") (pinfunction "1_1") (pintype "passive"))
      (node (ref "U1") (pin "P1") (pinfunction "~{CS}_P1") (pintype "bidirectional"))
      (node (ref "UC1") (pin "P$36") (pinfunction "PA17_P$36") (pintype "bidirectional"))
    )
    (net (code "139") (name "~{LED_CMD}") (class "Default")
      (node (ref "C28") (pin "1") (pinfunction "P$1_1") (pintype "passive"))
      (node (ref "R25") (pin "2") (pinfunction "2_2") (pintype "passive"))
      (node (ref "UC1") (pin "P$29") (pinfunction "PA12_P$29") (pintype "bidirectional"))
    )
    (net (code "140") (name "~{RAD_SHDN}") (class "Default")
      (node (ref "J8") (pin "P$5") (pinfunction "5_P$5") (pintype "bidirectional"))
      (node (ref "UC1") (pin "P$42") (pinfunction "PA21_P$42") (pintype "bidirectional"))
    )
    (net (code "141") (name "~{RESET}") (class "Default")
      (node (ref "J4") (pin "P$2") (pinfunction "P$2_P$2") (pintype "bidirectional"))
      (node (ref "J9") (pin "P6") (pinfunction "6_P6") (pintype "bidirectional"))
      (node (ref "UC1") (pin "P$52") (pinfunction "RESETN_P$52") (pintype "input"))
    )
  )
)
